# Olympus_v1.net
KiCad netlist of a schematic drawn in EAGLE
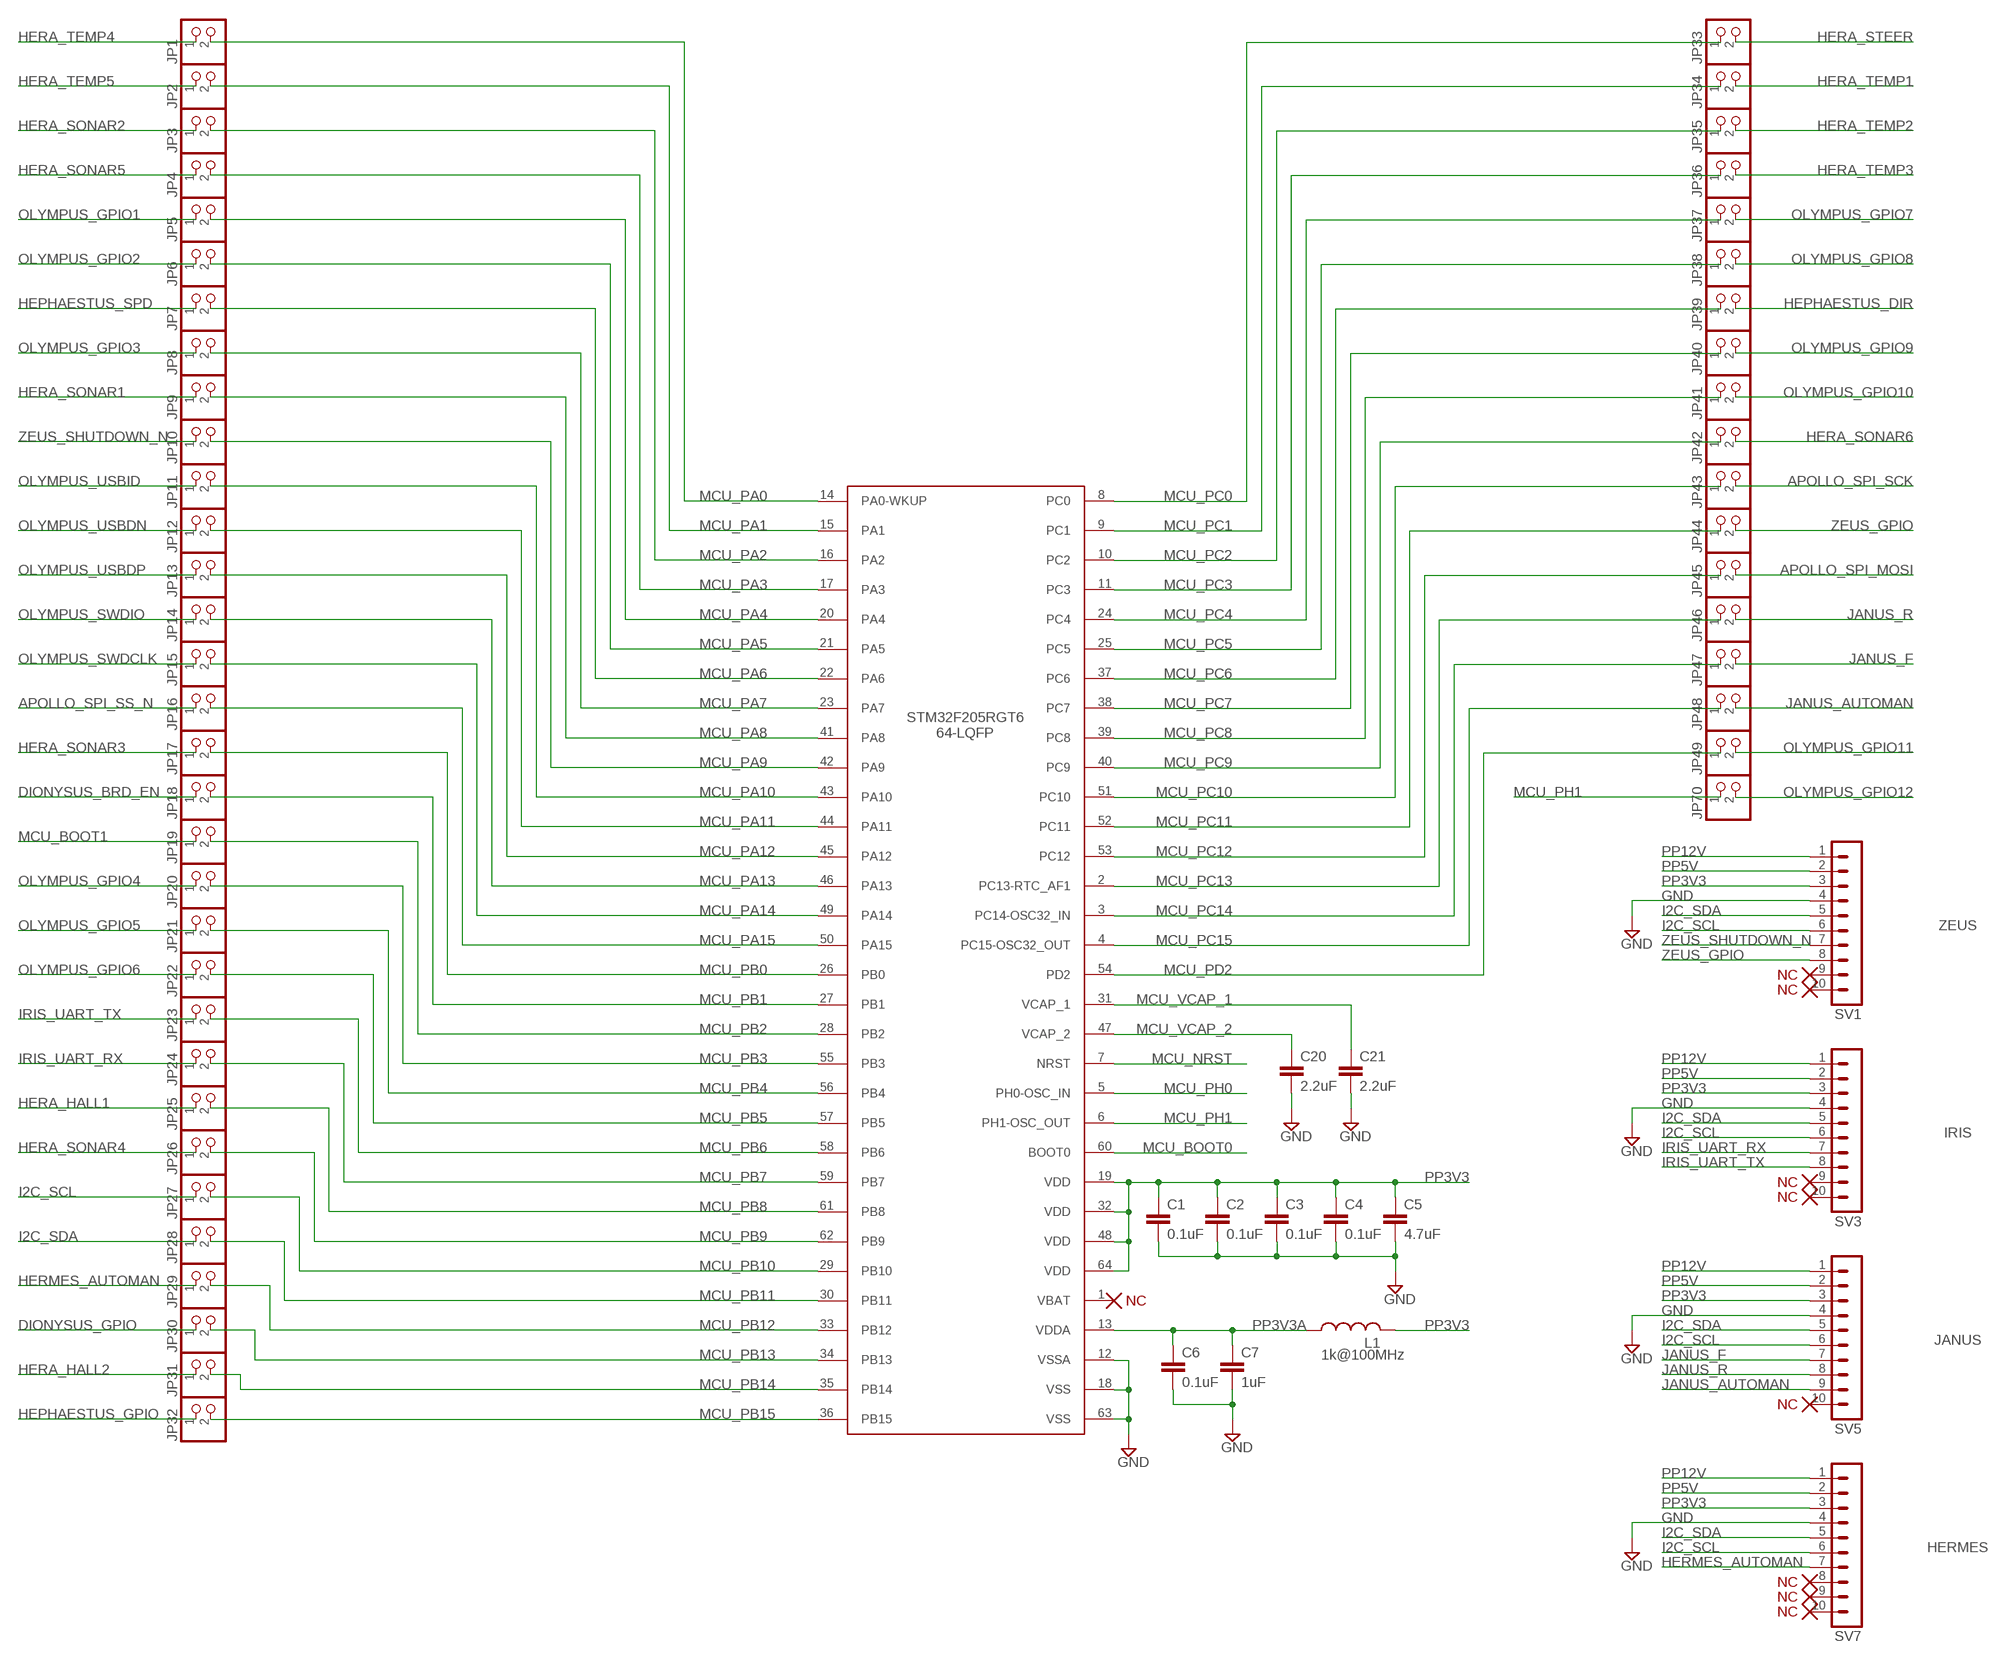
[diagram p0: schematic, sheet 1, part 1 of 2]
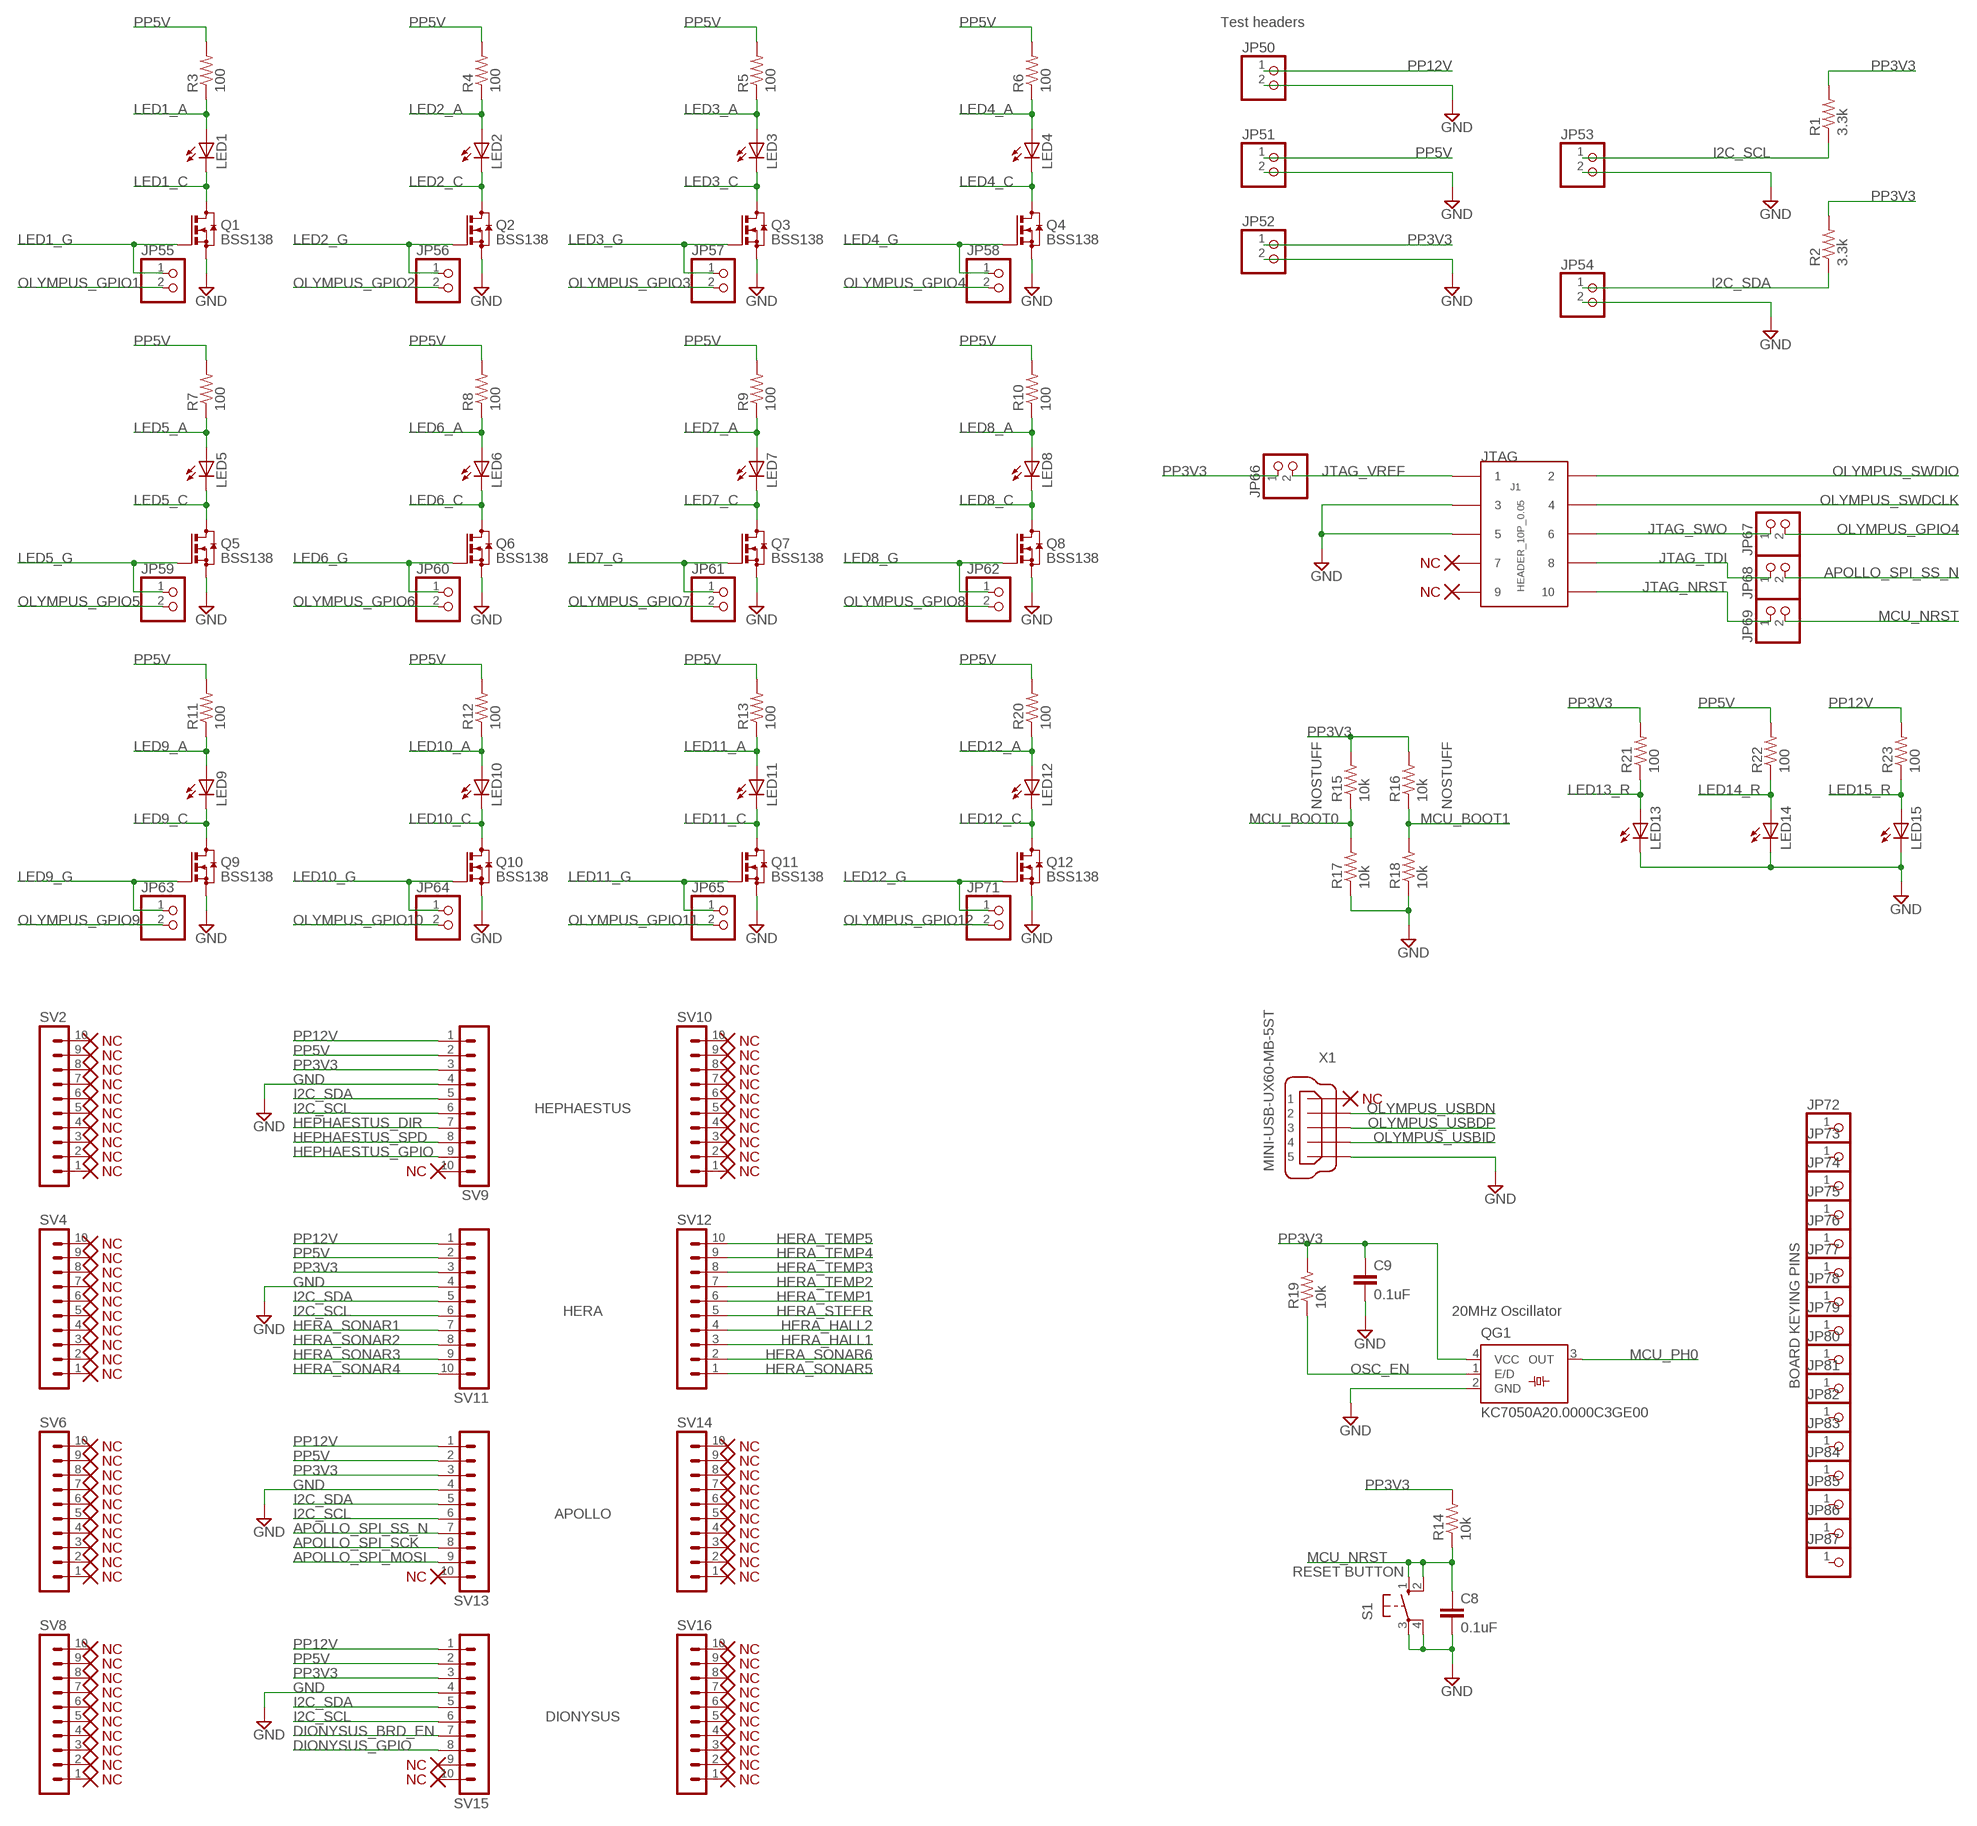
[diagram p1: schematic, sheet 1, part 2 of 2]

(export (version "E")
  (design (tool "Eeschema 10.0.6"))
  (components
    (comp (ref "C1")
      (value "0.1uF")
      (footprint "eagle-import:C0402")
      (libsource (lib "eagle-import") (part "C-EUC0402"))
    )
    (comp (ref "C2")
      (value "0.1uF")
      (footprint "eagle-import:C0402")
      (libsource (lib "eagle-import") (part "C-EUC0402"))
    )
    (comp (ref "C3")
      (value "0.1uF")
      (footprint "eagle-import:C0402")
      (libsource (lib "eagle-import") (part "C-EUC0402"))
    )
    (comp (ref "C4")
      (value "0.1uF")
      (footprint "eagle-import:C0402")
      (libsource (lib "eagle-import") (part "C-EUC0402"))
    )
    (comp (ref "C5")
      (value "4.7uF")
      (footprint "eagle-import:C0603")
      (libsource (lib "eagle-import") (part "C-EUC0603"))
    )
    (comp (ref "C6")
      (value "0.1uF")
      (footprint "eagle-import:C0402")
      (libsource (lib "eagle-import") (part "C-EUC0402"))
    )
    (comp (ref "C7")
      (value "1uF")
      (footprint "eagle-import:C0603")
      (libsource (lib "eagle-import") (part "C-EUC0603"))
    )
    (comp (ref "C8")
      (value "0.1uF")
      (footprint "eagle-import:C0402")
      (libsource (lib "eagle-import") (part "C-EUC0402"))
    )
    (comp (ref "C9")
      (value "0.1uF")
      (footprint "eagle-import:C0402")
      (libsource (lib "eagle-import") (part "C-EUC0402"))
    )
    (comp (ref "C20")
      (value "2.2uF")
      (footprint "eagle-import:C0402")
      (libsource (lib "eagle-import") (part "C-EUC0402"))
    )
    (comp (ref "C21")
      (value "2.2uF")
      (footprint "eagle-import:C0402")
      (libsource (lib "eagle-import") (part "C-EUC0402"))
    )
    (comp (ref "J1")
      (value "HEADER_10P_0.05")
      (footprint "eagle-import:HEADER_10P_0.05")
      (libsource (lib "eagle-import") (part "HEADER_10P_0.05"))
    )
    (comp (ref "JP1")
      (value "PINHD-1X2")
      (footprint "eagle-import:1X02")
      (libsource (lib "eagle-import") (part "PINHD-1X2"))
    )
    (comp (ref "JP2")
      (value "PINHD-1X2")
      (footprint "eagle-import:1X02")
      (libsource (lib "eagle-import") (part "PINHD-1X2"))
    )
    (comp (ref "JP3")
      (value "PINHD-1X2")
      (footprint "eagle-import:1X02")
      (libsource (lib "eagle-import") (part "PINHD-1X2"))
    )
    (comp (ref "JP4")
      (value "PINHD-1X2")
      (footprint "eagle-import:1X02")
      (libsource (lib "eagle-import") (part "PINHD-1X2"))
    )
    (comp (ref "JP5")
      (value "PINHD-1X2")
      (footprint "eagle-import:1X02")
      (libsource (lib "eagle-import") (part "PINHD-1X2"))
    )
    (comp (ref "JP6")
      (value "PINHD-1X2")
      (footprint "eagle-import:1X02")
      (libsource (lib "eagle-import") (part "PINHD-1X2"))
    )
    (comp (ref "JP7")
      (value "PINHD-1X2")
      (footprint "eagle-import:1X02")
      (libsource (lib "eagle-import") (part "PINHD-1X2"))
    )
    (comp (ref "JP8")
      (value "PINHD-1X2")
      (footprint "eagle-import:1X02")
      (libsource (lib "eagle-import") (part "PINHD-1X2"))
    )
    (comp (ref "JP9")
      (value "PINHD-1X2")
      (footprint "eagle-import:1X02")
      (libsource (lib "eagle-import") (part "PINHD-1X2"))
    )
    (comp (ref "JP10")
      (value "PINHD-1X2")
      (footprint "eagle-import:1X02")
      (libsource (lib "eagle-import") (part "PINHD-1X2"))
    )
    (comp (ref "JP11")
      (value "PINHD-1X2")
      (footprint "eagle-import:1X02")
      (libsource (lib "eagle-import") (part "PINHD-1X2"))
    )
    (comp (ref "JP12")
      (value "PINHD-1X2")
      (footprint "eagle-import:1X02")
      (libsource (lib "eagle-import") (part "PINHD-1X2"))
    )
    (comp (ref "JP13")
      (value "PINHD-1X2")
      (footprint "eagle-import:1X02")
      (libsource (lib "eagle-import") (part "PINHD-1X2"))
    )
    (comp (ref "JP14")
      (value "PINHD-1X2")
      (footprint "eagle-import:1X02")
      (libsource (lib "eagle-import") (part "PINHD-1X2"))
    )
    (comp (ref "JP15")
      (value "PINHD-1X2")
      (footprint "eagle-import:1X02")
      (libsource (lib "eagle-import") (part "PINHD-1X2"))
    )
    (comp (ref "JP16")
      (value "PINHD-1X2")
      (footprint "eagle-import:1X02")
      (libsource (lib "eagle-import") (part "PINHD-1X2"))
    )
    (comp (ref "JP17")
      (value "PINHD-1X2")
      (footprint "eagle-import:1X02")
      (libsource (lib "eagle-import") (part "PINHD-1X2"))
    )
    (comp (ref "JP18")
      (value "PINHD-1X2")
      (footprint "eagle-import:1X02")
      (libsource (lib "eagle-import") (part "PINHD-1X2"))
    )
    (comp (ref "JP19")
      (value "PINHD-1X2")
      (footprint "eagle-import:1X02")
      (libsource (lib "eagle-import") (part "PINHD-1X2"))
    )
    (comp (ref "JP20")
      (value "PINHD-1X2")
      (footprint "eagle-import:1X02")
      (libsource (lib "eagle-import") (part "PINHD-1X2"))
    )
    (comp (ref "JP21")
      (value "PINHD-1X2")
      (footprint "eagle-import:1X02")
      (libsource (lib "eagle-import") (part "PINHD-1X2"))
    )
    (comp (ref "JP22")
      (value "PINHD-1X2")
      (footprint "eagle-import:1X02")
      (libsource (lib "eagle-import") (part "PINHD-1X2"))
    )
    (comp (ref "JP23")
      (value "PINHD-1X2")
      (footprint "eagle-import:1X02")
      (libsource (lib "eagle-import") (part "PINHD-1X2"))
    )
    (comp (ref "JP24")
      (value "PINHD-1X2")
      (footprint "eagle-import:1X02")
      (libsource (lib "eagle-import") (part "PINHD-1X2"))
    )
    (comp (ref "JP25")
      (value "PINHD-1X2")
      (footprint "eagle-import:1X02")
      (libsource (lib "eagle-import") (part "PINHD-1X2"))
    )
    (comp (ref "JP26")
      (value "PINHD-1X2")
      (footprint "eagle-import:1X02")
      (libsource (lib "eagle-import") (part "PINHD-1X2"))
    )
    (comp (ref "JP27")
      (value "PINHD-1X2")
      (footprint "eagle-import:1X02")
      (libsource (lib "eagle-import") (part "PINHD-1X2"))
    )
    (comp (ref "JP28")
      (value "PINHD-1X2")
      (footprint "eagle-import:1X02")
      (libsource (lib "eagle-import") (part "PINHD-1X2"))
    )
    (comp (ref "JP29")
      (value "PINHD-1X2")
      (footprint "eagle-import:1X02")
      (libsource (lib "eagle-import") (part "PINHD-1X2"))
    )
    (comp (ref "JP30")
      (value "PINHD-1X2")
      (footprint "eagle-import:1X02")
      (libsource (lib "eagle-import") (part "PINHD-1X2"))
    )
    (comp (ref "JP31")
      (value "PINHD-1X2")
      (footprint "eagle-import:1X02")
      (libsource (lib "eagle-import") (part "PINHD-1X2"))
    )
    (comp (ref "JP32")
      (value "PINHD-1X2")
      (footprint "eagle-import:1X02")
      (libsource (lib "eagle-import") (part "PINHD-1X2"))
    )
    (comp (ref "JP33")
      (value "PINHD-1X2")
      (footprint "eagle-import:1X02")
      (libsource (lib "eagle-import") (part "PINHD-1X2"))
    )
    (comp (ref "JP34")
      (value "PINHD-1X2")
      (footprint "eagle-import:1X02")
      (libsource (lib "eagle-import") (part "PINHD-1X2"))
    )
    (comp (ref "JP35")
      (value "PINHD-1X2")
      (footprint "eagle-import:1X02")
      (libsource (lib "eagle-import") (part "PINHD-1X2"))
    )
    (comp (ref "JP36")
      (value "PINHD-1X2")
      (footprint "eagle-import:1X02")
      (libsource (lib "eagle-import") (part "PINHD-1X2"))
    )
    (comp (ref "JP37")
      (value "PINHD-1X2")
      (footprint "eagle-import:1X02")
      (libsource (lib "eagle-import") (part "PINHD-1X2"))
    )
    (comp (ref "JP38")
      (value "PINHD-1X2")
      (footprint "eagle-import:1X02")
      (libsource (lib "eagle-import") (part "PINHD-1X2"))
    )
    (comp (ref "JP39")
      (value "PINHD-1X2")
      (footprint "eagle-import:1X02")
      (libsource (lib "eagle-import") (part "PINHD-1X2"))
    )
    (comp (ref "JP40")
      (value "PINHD-1X2")
      (footprint "eagle-import:1X02")
      (libsource (lib "eagle-import") (part "PINHD-1X2"))
    )
    (comp (ref "JP41")
      (value "PINHD-1X2")
      (footprint "eagle-import:1X02")
      (libsource (lib "eagle-import") (part "PINHD-1X2"))
    )
    (comp (ref "JP42")
      (value "PINHD-1X2")
      (footprint "eagle-import:1X02")
      (libsource (lib "eagle-import") (part "PINHD-1X2"))
    )
    (comp (ref "JP43")
      (value "PINHD-1X2")
      (footprint "eagle-import:1X02")
      (libsource (lib "eagle-import") (part "PINHD-1X2"))
    )
    (comp (ref "JP44")
      (value "PINHD-1X2")
      (footprint "eagle-import:1X02")
      (libsource (lib "eagle-import") (part "PINHD-1X2"))
    )
    (comp (ref "JP45")
      (value "PINHD-1X2")
      (footprint "eagle-import:1X02")
      (libsource (lib "eagle-import") (part "PINHD-1X2"))
    )
    (comp (ref "JP46")
      (value "PINHD-1X2")
      (footprint "eagle-import:1X02")
      (libsource (lib "eagle-import") (part "PINHD-1X2"))
    )
    (comp (ref "JP47")
      (value "PINHD-1X2")
      (footprint "eagle-import:1X02")
      (libsource (lib "eagle-import") (part "PINHD-1X2"))
    )
    (comp (ref "JP48")
      (value "PINHD-1X2")
      (footprint "eagle-import:1X02")
      (libsource (lib "eagle-import") (part "PINHD-1X2"))
    )
    (comp (ref "JP49")
      (value "PINHD-1X2")
      (footprint "eagle-import:1X02")
      (libsource (lib "eagle-import") (part "PINHD-1X2"))
    )
    (comp (ref "JP50")
      (value "PINHD-1X2")
      (footprint "eagle-import:1X02")
      (libsource (lib "eagle-import") (part "PINHD-1X2"))
    )
    (comp (ref "JP51")
      (value "PINHD-1X2")
      (footprint "eagle-import:1X02")
      (libsource (lib "eagle-import") (part "PINHD-1X2"))
    )
    (comp (ref "JP52")
      (value "PINHD-1X2")
      (footprint "eagle-import:1X02")
      (libsource (lib "eagle-import") (part "PINHD-1X2"))
    )
    (comp (ref "JP53")
      (value "PINHD-1X2")
      (footprint "eagle-import:1X02")
      (libsource (lib "eagle-import") (part "PINHD-1X2"))
    )
    (comp (ref "JP54")
      (value "PINHD-1X2")
      (footprint "eagle-import:1X02")
      (libsource (lib "eagle-import") (part "PINHD-1X2"))
    )
    (comp (ref "JP55")
      (value "PINHD-1X2")
      (footprint "eagle-import:1X02")
      (libsource (lib "eagle-import") (part "PINHD-1X2"))
    )
    (comp (ref "JP56")
      (value "PINHD-1X2")
      (footprint "eagle-import:1X02")
      (libsource (lib "eagle-import") (part "PINHD-1X2"))
    )
    (comp (ref "JP57")
      (value "PINHD-1X2")
      (footprint "eagle-import:1X02")
      (libsource (lib "eagle-import") (part "PINHD-1X2"))
    )
    (comp (ref "JP58")
      (value "PINHD-1X2")
      (footprint "eagle-import:1X02")
      (libsource (lib "eagle-import") (part "PINHD-1X2"))
    )
    (comp (ref "JP59")
      (value "PINHD-1X2")
      (footprint "eagle-import:1X02")
      (libsource (lib "eagle-import") (part "PINHD-1X2"))
    )
    (comp (ref "JP60")
      (value "PINHD-1X2")
      (footprint "eagle-import:1X02")
      (libsource (lib "eagle-import") (part "PINHD-1X2"))
    )
    (comp (ref "JP61")
      (value "PINHD-1X2")
      (footprint "eagle-import:1X02")
      (libsource (lib "eagle-import") (part "PINHD-1X2"))
    )
    (comp (ref "JP62")
      (value "PINHD-1X2")
      (footprint "eagle-import:1X02")
      (libsource (lib "eagle-import") (part "PINHD-1X2"))
    )
    (comp (ref "JP63")
      (value "PINHD-1X2")
      (footprint "eagle-import:1X02")
      (libsource (lib "eagle-import") (part "PINHD-1X2"))
    )
    (comp (ref "JP64")
      (value "PINHD-1X2")
      (footprint "eagle-import:1X02")
      (libsource (lib "eagle-import") (part "PINHD-1X2"))
    )
    (comp (ref "JP65")
      (value "PINHD-1X2")
      (footprint "eagle-import:1X02")
      (libsource (lib "eagle-import") (part "PINHD-1X2"))
    )
    (comp (ref "JP66")
      (value "PINHD-1X2")
      (footprint "eagle-import:1X02")
      (libsource (lib "eagle-import") (part "PINHD-1X2"))
    )
    (comp (ref "JP67")
      (value "PINHD-1X2")
      (footprint "eagle-import:1X02")
      (libsource (lib "eagle-import") (part "PINHD-1X2"))
    )
    (comp (ref "JP68")
      (value "PINHD-1X2")
      (footprint "eagle-import:1X02")
      (libsource (lib "eagle-import") (part "PINHD-1X2"))
    )
    (comp (ref "JP69")
      (value "PINHD-1X2")
      (footprint "eagle-import:1X02")
      (libsource (lib "eagle-import") (part "PINHD-1X2"))
    )
    (comp (ref "JP70")
      (value "PINHD-1X2")
      (footprint "eagle-import:1X02")
      (libsource (lib "eagle-import") (part "PINHD-1X2"))
    )
    (comp (ref "JP71")
      (value "PINHD-1X2")
      (footprint "eagle-import:1X02")
      (libsource (lib "eagle-import") (part "PINHD-1X2"))
    )
    (comp (ref "JP72")
      (value "PINHD-1X1")
      (footprint "eagle-import:1X01")
      (libsource (lib "eagle-import") (part "PINHD-1X1"))
    )
    (comp (ref "JP73")
      (value "PINHD-1X1")
      (footprint "eagle-import:1X01")
      (libsource (lib "eagle-import") (part "PINHD-1X1"))
    )
    (comp (ref "JP74")
      (value "PINHD-1X1")
      (footprint "eagle-import:1X01")
      (libsource (lib "eagle-import") (part "PINHD-1X1"))
    )
    (comp (ref "JP75")
      (value "PINHD-1X1")
      (footprint "eagle-import:1X01")
      (libsource (lib "eagle-import") (part "PINHD-1X1"))
    )
    (comp (ref "JP76")
      (value "PINHD-1X1")
      (footprint "eagle-import:1X01")
      (libsource (lib "eagle-import") (part "PINHD-1X1"))
    )
    (comp (ref "JP77")
      (value "PINHD-1X1")
      (footprint "eagle-import:1X01")
      (libsource (lib "eagle-import") (part "PINHD-1X1"))
    )
    (comp (ref "JP78")
      (value "PINHD-1X1")
      (footprint "eagle-import:1X01")
      (libsource (lib "eagle-import") (part "PINHD-1X1"))
    )
    (comp (ref "JP79")
      (value "PINHD-1X1")
      (footprint "eagle-import:1X01")
      (libsource (lib "eagle-import") (part "PINHD-1X1"))
    )
    (comp (ref "JP80")
      (value "PINHD-1X1")
      (footprint "eagle-import:1X01")
      (libsource (lib "eagle-import") (part "PINHD-1X1"))
    )
    (comp (ref "JP81")
      (value "PINHD-1X1")
      (footprint "eagle-import:1X01")
      (libsource (lib "eagle-import") (part "PINHD-1X1"))
    )
    (comp (ref "JP82")
      (value "PINHD-1X1")
      (footprint "eagle-import:1X01")
      (libsource (lib "eagle-import") (part "PINHD-1X1"))
    )
    (comp (ref "JP83")
      (value "PINHD-1X1")
      (footprint "eagle-import:1X01")
      (libsource (lib "eagle-import") (part "PINHD-1X1"))
    )
    (comp (ref "JP84")
      (value "PINHD-1X1")
      (footprint "eagle-import:1X01")
      (libsource (lib "eagle-import") (part "PINHD-1X1"))
    )
    (comp (ref "JP85")
      (value "PINHD-1X1")
      (footprint "eagle-import:1X01")
      (libsource (lib "eagle-import") (part "PINHD-1X1"))
    )
    (comp (ref "JP86")
      (value "PINHD-1X1")
      (footprint "eagle-import:1X01")
      (libsource (lib "eagle-import") (part "PINHD-1X1"))
    )
    (comp (ref "JP87")
      (value "PINHD-1X1")
      (footprint "eagle-import:1X01")
      (libsource (lib "eagle-import") (part "PINHD-1X1"))
    )
    (comp (ref "L1")
      (value "L-USL0201")
      (footprint "eagle-import:L0201")
      (libsource (lib "eagle-import") (part "L-USL0201"))
    )
    (comp (ref "LED1")
      (value "LEDCHIP-LED0603")
      (footprint "eagle-import:CHIP-LED0603")
      (libsource (lib "eagle-import") (part "LEDCHIP-LED0603"))
    )
    (comp (ref "LED2")
      (value "LEDCHIP-LED0603")
      (footprint "eagle-import:CHIP-LED0603")
      (libsource (lib "eagle-import") (part "LEDCHIP-LED0603"))
    )
    (comp (ref "LED3")
      (value "LEDCHIP-LED0603")
      (footprint "eagle-import:CHIP-LED0603")
      (libsource (lib "eagle-import") (part "LEDCHIP-LED0603"))
    )
    (comp (ref "LED4")
      (value "LEDCHIP-LED0603")
      (footprint "eagle-import:CHIP-LED0603")
      (libsource (lib "eagle-import") (part "LEDCHIP-LED0603"))
    )
    (comp (ref "LED5")
      (value "LEDCHIP-LED0603")
      (footprint "eagle-import:CHIP-LED0603")
      (libsource (lib "eagle-import") (part "LEDCHIP-LED0603"))
    )
    (comp (ref "LED6")
      (value "LEDCHIP-LED0603")
      (footprint "eagle-import:CHIP-LED0603")
      (libsource (lib "eagle-import") (part "LEDCHIP-LED0603"))
    )
    (comp (ref "LED7")
      (value "LEDCHIP-LED0603")
      (footprint "eagle-import:CHIP-LED0603")
      (libsource (lib "eagle-import") (part "LEDCHIP-LED0603"))
    )
    (comp (ref "LED8")
      (value "LEDCHIP-LED0603")
      (footprint "eagle-import:CHIP-LED0603")
      (libsource (lib "eagle-import") (part "LEDCHIP-LED0603"))
    )
    (comp (ref "LED9")
      (value "LEDCHIP-LED0603")
      (footprint "eagle-import:CHIP-LED0603")
      (libsource (lib "eagle-import") (part "LEDCHIP-LED0603"))
    )
    (comp (ref "LED10")
      (value "LEDCHIP-LED0603")
      (footprint "eagle-import:CHIP-LED0603")
      (libsource (lib "eagle-import") (part "LEDCHIP-LED0603"))
    )
    (comp (ref "LED11")
      (value "LEDCHIP-LED0603")
      (footprint "eagle-import:CHIP-LED0603")
      (libsource (lib "eagle-import") (part "LEDCHIP-LED0603"))
    )
    (comp (ref "LED12")
      (value "LEDCHIP-LED0603")
      (footprint "eagle-import:CHIP-LED0603")
      (libsource (lib "eagle-import") (part "LEDCHIP-LED0603"))
    )
    (comp (ref "LED13")
      (value "LEDCHIP-LED0603")
      (footprint "eagle-import:CHIP-LED0603")
      (libsource (lib "eagle-import") (part "LEDCHIP-LED0603"))
    )
    (comp (ref "LED14")
      (value "LEDCHIP-LED0603")
      (footprint "eagle-import:CHIP-LED0603")
      (libsource (lib "eagle-import") (part "LEDCHIP-LED0603"))
    )
    (comp (ref "LED15")
      (value "LEDCHIP-LED0603")
      (footprint "eagle-import:CHIP-LED0603")
      (libsource (lib "eagle-import") (part "LEDCHIP-LED0603"))
    )
    (comp (ref "Q1")
      (value "BSS138")
      (footprint "eagle-import:SOT23")
      (libsource (lib "eagle-import") (part "BSS123"))
    )
    (comp (ref "Q2")
      (value "BSS138")
      (footprint "eagle-import:SOT23")
      (libsource (lib "eagle-import") (part "BSS123"))
    )
    (comp (ref "Q3")
      (value "BSS138")
      (footprint "eagle-import:SOT23")
      (libsource (lib "eagle-import") (part "BSS123"))
    )
    (comp (ref "Q4")
      (value "BSS138")
      (footprint "eagle-import:SOT23")
      (libsource (lib "eagle-import") (part "BSS123"))
    )
    (comp (ref "Q5")
      (value "BSS138")
      (footprint "eagle-import:SOT23")
      (libsource (lib "eagle-import") (part "BSS123"))
    )
    (comp (ref "Q6")
      (value "BSS138")
      (footprint "eagle-import:SOT23")
      (libsource (lib "eagle-import") (part "BSS123"))
    )
    (comp (ref "Q7")
      (value "BSS138")
      (footprint "eagle-import:SOT23")
      (libsource (lib "eagle-import") (part "BSS123"))
    )
    (comp (ref "Q8")
      (value "BSS138")
      (footprint "eagle-import:SOT23")
      (libsource (lib "eagle-import") (part "BSS123"))
    )
    (comp (ref "Q9")
      (value "BSS138")
      (footprint "eagle-import:SOT23")
      (libsource (lib "eagle-import") (part "BSS123"))
    )
    (comp (ref "Q10")
      (value "BSS138")
      (footprint "eagle-import:SOT23")
      (libsource (lib "eagle-import") (part "BSS123"))
    )
    (comp (ref "Q11")
      (value "BSS138")
      (footprint "eagle-import:SOT23")
      (libsource (lib "eagle-import") (part "BSS123"))
    )
    (comp (ref "Q12")
      (value "BSS138")
      (footprint "eagle-import:SOT23")
      (libsource (lib "eagle-import") (part "BSS123"))
    )
    (comp (ref "QG1")
      (value "KC7050A20.0000C3GE00")
      (footprint "eagle-import:SM77H")
      (libsource (lib "eagle-import") (part "SM77H"))
    )
    (comp (ref "R1")
      (value "3.3k")
      (footprint "eagle-import:R0603")
      (libsource (lib "eagle-import") (part "R-US_R0603"))
    )
    (comp (ref "R2")
      (value "3.3k")
      (footprint "eagle-import:R0603")
      (libsource (lib "eagle-import") (part "R-US_R0603"))
    )
    (comp (ref "R3")
      (value "100")
      (footprint "eagle-import:R0603")
      (libsource (lib "eagle-import") (part "resistor_R-US_R0603"))
    )
    (comp (ref "R4")
      (value "100")
      (footprint "eagle-import:R0603")
      (libsource (lib "eagle-import") (part "resistor_R-US_R0603"))
    )
    (comp (ref "R5")
      (value "100")
      (footprint "eagle-import:R0603")
      (libsource (lib "eagle-import") (part "resistor_R-US_R0603"))
    )
    (comp (ref "R6")
      (value "100")
      (footprint "eagle-import:R0603")
      (libsource (lib "eagle-import") (part "resistor_R-US_R0603"))
    )
    (comp (ref "R7")
      (value "100")
      (footprint "eagle-import:R0603")
      (libsource (lib "eagle-import") (part "resistor_R-US_R0603"))
    )
    (comp (ref "R8")
      (value "100")
      (footprint "eagle-import:R0603")
      (libsource (lib "eagle-import") (part "resistor_R-US_R0603"))
    )
    (comp (ref "R9")
      (value "100")
      (footprint "eagle-import:R0603")
      (libsource (lib "eagle-import") (part "resistor_R-US_R0603"))
    )
    (comp (ref "R10")
      (value "100")
      (footprint "eagle-import:R0603")
      (libsource (lib "eagle-import") (part "resistor_R-US_R0603"))
    )
    (comp (ref "R11")
      (value "100")
      (footprint "eagle-import:R0603")
      (libsource (lib "eagle-import") (part "resistor_R-US_R0603"))
    )
    (comp (ref "R12")
      (value "100")
      (footprint "eagle-import:R0603")
      (libsource (lib "eagle-import") (part "resistor_R-US_R0603"))
    )
    (comp (ref "R13")
      (value "100")
      (footprint "eagle-import:R0603")
      (libsource (lib "eagle-import") (part "resistor_R-US_R0603"))
    )
    (comp (ref "R14")
      (value "10k")
      (footprint "eagle-import:R0603")
      (libsource (lib "eagle-import") (part "R-US_R0603"))
    )
    (comp (ref "R15")
      (value "10k")
      (footprint "eagle-import:R0603")
      (fields (field (name "BOMOPTION") "NOSTUFF"))
      (libsource (lib "eagle-import") (part "R-US_R0603"))
    )
    (comp (ref "R16")
      (value "10k")
      (footprint "eagle-import:R0603")
      (fields (field (name "BOMOPTION") "NOSTUFF"))
      (libsource (lib "eagle-import") (part "R-US_R0603"))
    )
    (comp (ref "R17")
      (value "10k")
      (footprint "eagle-import:R0603")
      (libsource (lib "eagle-import") (part "R-US_R0603"))
    )
    (comp (ref "R18")
      (value "10k")
      (footprint "eagle-import:R0603")
      (libsource (lib "eagle-import") (part "R-US_R0603"))
    )
    (comp (ref "R19")
      (value "10k")
      (footprint "eagle-import:R0603")
      (libsource (lib "eagle-import") (part "R-US_R0603"))
    )
    (comp (ref "R20")
      (value "100")
      (footprint "eagle-import:R0603")
      (libsource (lib "eagle-import") (part "resistor_R-US_R0603"))
    )
    (comp (ref "R21")
      (value "100")
      (footprint "eagle-import:R0603")
      (libsource (lib "eagle-import") (part "resistor_R-US_R0603"))
    )
    (comp (ref "R22")
      (value "100")
      (footprint "eagle-import:R0603")
      (libsource (lib "eagle-import") (part "resistor_R-US_R0603"))
    )
    (comp (ref "R23")
      (value "100")
      (footprint "eagle-import:R0603")
      (libsource (lib "eagle-import") (part "resistor_R-US_R0603"))
    )
    (comp (ref "S1")
      (value "10-XX")
      (footprint "eagle-import:B3F-10XX")
      (fields (field (name "MPN") "B3F-1000"))
      (libsource (lib "eagle-import") (part "10-XX"))
    )
    (comp (ref "SV1")
      (value "MA10-1")
      (footprint "eagle-import:MA10-1")
      (libsource (lib "eagle-import") (part "MA10-1"))
    )
    (comp (ref "SV2")
      (value "MA10-1")
      (footprint "eagle-import:MA10-1")
      (libsource (lib "eagle-import") (part "MA10-1"))
    )
    (comp (ref "SV3")
      (value "MA10-1")
      (footprint "eagle-import:MA10-1")
      (libsource (lib "eagle-import") (part "MA10-1"))
    )
    (comp (ref "SV4")
      (value "MA10-1")
      (footprint "eagle-import:MA10-1")
      (libsource (lib "eagle-import") (part "MA10-1"))
    )
    (comp (ref "SV5")
      (value "MA10-1")
      (footprint "eagle-import:MA10-1")
      (libsource (lib "eagle-import") (part "MA10-1"))
    )
    (comp (ref "SV6")
      (value "MA10-1")
      (footprint "eagle-import:MA10-1")
      (libsource (lib "eagle-import") (part "MA10-1"))
    )
    (comp (ref "SV7")
      (value "MA10-1")
      (footprint "eagle-import:MA10-1")
      (libsource (lib "eagle-import") (part "MA10-1"))
    )
    (comp (ref "SV8")
      (value "MA10-1")
      (footprint "eagle-import:MA10-1")
      (libsource (lib "eagle-import") (part "MA10-1"))
    )
    (comp (ref "SV9")
      (value "MA10-1")
      (footprint "eagle-import:MA10-1")
      (libsource (lib "eagle-import") (part "MA10-1"))
    )
    (comp (ref "SV10")
      (value "MA10-1")
      (footprint "eagle-import:MA10-1")
      (libsource (lib "eagle-import") (part "MA10-1"))
    )
    (comp (ref "SV11")
      (value "MA10-1")
      (footprint "eagle-import:MA10-1")
      (libsource (lib "eagle-import") (part "MA10-1"))
    )
    (comp (ref "SV12")
      (value "MA10-1")
      (footprint "eagle-import:MA10-1")
      (libsource (lib "eagle-import") (part "MA10-1"))
    )
    (comp (ref "SV13")
      (value "MA10-1")
      (footprint "eagle-import:MA10-1")
      (libsource (lib "eagle-import") (part "MA10-1"))
    )
    (comp (ref "SV14")
      (value "MA10-1")
      (footprint "eagle-import:MA10-1")
      (libsource (lib "eagle-import") (part "MA10-1"))
    )
    (comp (ref "SV15")
      (value "MA10-1")
      (footprint "eagle-import:MA10-1")
      (libsource (lib "eagle-import") (part "MA10-1"))
    )
    (comp (ref "SV16")
      (value "MA10-1")
      (footprint "eagle-import:MA10-1")
      (libsource (lib "eagle-import") (part "MA10-1"))
    )
    (comp (ref "U1")
      (value "STM32F205RGT6")
      (footprint "eagle-import:LQFP-ST-64-2")
      (libsource (lib "eagle-import") (part "STM32F205RGT6"))
    )
    (comp (ref "X1")
      (value "MINI-USB-UX60-MB-5ST")
      (footprint "eagle-import:UX60-MB-5ST")
      (libsource (lib "eagle-import") (part "MINI-USB-UX60-MB-5ST"))
    )
  )
  (nets
    (net (code "1") (name "/APOLLO_SPI_MOSI") (class "Default")
      (node (ref "JP45") (pin "2") (pinfunction "2_2") (pintype "passive"))
      (node (ref "SV13") (pin "9") (pinfunction "9_9") (pintype "passive"))
    )
    (net (code "2") (name "/APOLLO_SPI_SCK") (class "Default")
      (node (ref "JP43") (pin "2") (pinfunction "2_2") (pintype "passive"))
      (node (ref "SV13") (pin "8") (pinfunction "8_8") (pintype "passive"))
    )
    (net (code "3") (name "/APOLLO_SPI_SS_N") (class "Default")
      (node (ref "JP16") (pin "1") (pinfunction "1_1") (pintype "passive"))
      (node (ref "JP68") (pin "2") (pinfunction "2_2") (pintype "passive"))
      (node (ref "SV13") (pin "7") (pinfunction "7_7") (pintype "passive"))
    )
    (net (code "4") (name "/DIONYSUS_BRD_EN") (class "Default")
      (node (ref "JP18") (pin "1") (pinfunction "1_1") (pintype "passive"))
      (node (ref "SV15") (pin "7") (pinfunction "7_7") (pintype "passive"))
    )
    (net (code "5") (name "/DIONYSUS_GPIO") (class "Default")
      (node (ref "JP30") (pin "1") (pinfunction "1_1") (pintype "passive"))
      (node (ref "SV15") (pin "8") (pinfunction "8_8") (pintype "passive"))
    )
    (net (code "6") (name "/HEPHAESTUS_DIR") (class "Default")
      (node (ref "JP39") (pin "2") (pinfunction "2_2") (pintype "passive"))
      (node (ref "SV9") (pin "7") (pinfunction "7_7") (pintype "passive"))
    )
    (net (code "7") (name "/HEPHAESTUS_GPIO") (class "Default")
      (node (ref "JP32") (pin "1") (pinfunction "1_1") (pintype "passive"))
      (node (ref "SV9") (pin "9") (pinfunction "9_9") (pintype "passive"))
    )
    (net (code "8") (name "/HEPHAESTUS_SPD") (class "Default")
      (node (ref "JP7") (pin "1") (pinfunction "1_1") (pintype "passive"))
      (node (ref "SV9") (pin "8") (pinfunction "8_8") (pintype "passive"))
    )
    (net (code "9") (name "/HERA_HALL1") (class "Default")
      (node (ref "JP25") (pin "1") (pinfunction "1_1") (pintype "passive"))
      (node (ref "SV12") (pin "3") (pinfunction "3_3") (pintype "passive"))
    )
    (net (code "10") (name "/HERA_HALL2") (class "Default")
      (node (ref "JP31") (pin "1") (pinfunction "1_1") (pintype "passive"))
      (node (ref "SV12") (pin "4") (pinfunction "4_4") (pintype "passive"))
    )
    (net (code "11") (name "/HERA_SONAR1") (class "Default")
      (node (ref "JP9") (pin "1") (pinfunction "1_1") (pintype "passive"))
      (node (ref "SV11") (pin "7") (pinfunction "7_7") (pintype "passive"))
    )
    (net (code "12") (name "/HERA_SONAR2") (class "Default")
      (node (ref "JP3") (pin "1") (pinfunction "1_1") (pintype "passive"))
      (node (ref "SV11") (pin "8") (pinfunction "8_8") (pintype "passive"))
    )
    (net (code "13") (name "/HERA_SONAR3") (class "Default")
      (node (ref "JP17") (pin "1") (pinfunction "1_1") (pintype "passive"))
      (node (ref "SV11") (pin "9") (pinfunction "9_9") (pintype "passive"))
    )
    (net (code "14") (name "/HERA_SONAR4") (class "Default")
      (node (ref "JP26") (pin "1") (pinfunction "1_1") (pintype "passive"))
      (node (ref "SV11") (pin "10") (pinfunction "10_10") (pintype "passive"))
    )
    (net (code "15") (name "/HERA_SONAR5") (class "Default")
      (node (ref "JP4") (pin "1") (pinfunction "1_1") (pintype "passive"))
      (node (ref "SV12") (pin "1") (pinfunction "1_1") (pintype "passive"))
    )
    (net (code "16") (name "/HERA_SONAR6") (class "Default")
      (node (ref "JP42") (pin "2") (pinfunction "2_2") (pintype "passive"))
      (node (ref "SV12") (pin "2") (pinfunction "2_2") (pintype "passive"))
    )
    (net (code "17") (name "/HERA_STEER") (class "Default")
      (node (ref "JP33") (pin "2") (pinfunction "2_2") (pintype "passive"))
      (node (ref "SV12") (pin "5") (pinfunction "5_5") (pintype "passive"))
    )
    (net (code "18") (name "/HERA_TEMP1") (class "Default")
      (node (ref "JP34") (pin "2") (pinfunction "2_2") (pintype "passive"))
      (node (ref "SV12") (pin "6") (pinfunction "6_6") (pintype "passive"))
    )
    (net (code "19") (name "/HERA_TEMP2") (class "Default")
      (node (ref "JP35") (pin "2") (pinfunction "2_2") (pintype "passive"))
      (node (ref "SV12") (pin "7") (pinfunction "7_7") (pintype "passive"))
    )
    (net (code "20") (name "/HERA_TEMP3") (class "Default")
      (node (ref "JP36") (pin "2") (pinfunction "2_2") (pintype "passive"))
      (node (ref "SV12") (pin "8") (pinfunction "8_8") (pintype "passive"))
    )
    (net (code "21") (name "/HERA_TEMP4") (class "Default")
      (node (ref "JP1") (pin "1") (pinfunction "1_1") (pintype "passive"))
      (node (ref "SV12") (pin "9") (pinfunction "9_9") (pintype "passive"))
    )
    (net (code "22") (name "/HERA_TEMP5") (class "Default")
      (node (ref "JP2") (pin "1") (pinfunction "1_1") (pintype "passive"))
      (node (ref "SV12") (pin "10") (pinfunction "10_10") (pintype "passive"))
    )
    (net (code "23") (name "/HERMES_AUTOMAN") (class "Default")
      (node (ref "JP29") (pin "1") (pinfunction "1_1") (pintype "passive"))
      (node (ref "SV7") (pin "7") (pinfunction "7_7") (pintype "passive"))
    )
    (net (code "24") (name "/I2C_SCL") (class "Default")
      (node (ref "JP27") (pin "1") (pinfunction "1_1") (pintype "passive"))
      (node (ref "JP53") (pin "1") (pinfunction "1_1") (pintype "passive"))
      (node (ref "R1") (pin "1") (pinfunction "1_1") (pintype "passive"))
      (node (ref "SV1") (pin "6") (pinfunction "6_6") (pintype "passive"))
      (node (ref "SV11") (pin "6") (pinfunction "6_6") (pintype "passive"))
      (node (ref "SV13") (pin "6") (pinfunction "6_6") (pintype "passive"))
      (node (ref "SV15") (pin "6") (pinfunction "6_6") (pintype "passive"))
      (node (ref "SV3") (pin "6") (pinfunction "6_6") (pintype "passive"))
      (node (ref "SV5") (pin "6") (pinfunction "6_6") (pintype "passive"))
      (node (ref "SV7") (pin "6") (pinfunction "6_6") (pintype "passive"))
      (node (ref "SV9") (pin "6") (pinfunction "6_6") (pintype "passive"))
    )
    (net (code "25") (name "/I2C_SDA") (class "Default")
      (node (ref "JP28") (pin "1") (pinfunction "1_1") (pintype "passive"))
      (node (ref "JP54") (pin "1") (pinfunction "1_1") (pintype "passive"))
      (node (ref "R2") (pin "1") (pinfunction "1_1") (pintype "passive"))
      (node (ref "SV1") (pin "5") (pinfunction "5_5") (pintype "passive"))
      (node (ref "SV11") (pin "5") (pinfunction "5_5") (pintype "passive"))
      (node (ref "SV13") (pin "5") (pinfunction "5_5") (pintype "passive"))
      (node (ref "SV15") (pin "5") (pinfunction "5_5") (pintype "passive"))
      (node (ref "SV3") (pin "5") (pinfunction "5_5") (pintype "passive"))
      (node (ref "SV5") (pin "5") (pinfunction "5_5") (pintype "passive"))
      (node (ref "SV7") (pin "5") (pinfunction "5_5") (pintype "passive"))
      (node (ref "SV9") (pin "5") (pinfunction "5_5") (pintype "passive"))
    )
    (net (code "26") (name "/IRIS_UART_RX") (class "Default")
      (node (ref "JP24") (pin "1") (pinfunction "1_1") (pintype "passive"))
      (node (ref "SV3") (pin "7") (pinfunction "7_7") (pintype "passive"))
    )
    (net (code "27") (name "/IRIS_UART_TX") (class "Default")
      (node (ref "JP23") (pin "1") (pinfunction "1_1") (pintype "passive"))
      (node (ref "SV3") (pin "8") (pinfunction "8_8") (pintype "passive"))
    )
    (net (code "28") (name "/JANUS_AUTOMAN") (class "Default")
      (node (ref "JP48") (pin "2") (pinfunction "2_2") (pintype "passive"))
      (node (ref "SV5") (pin "9") (pinfunction "9_9") (pintype "passive"))
    )
    (net (code "29") (name "/JANUS_F") (class "Default")
      (node (ref "JP47") (pin "2") (pinfunction "2_2") (pintype "passive"))
      (node (ref "SV5") (pin "7") (pinfunction "7_7") (pintype "passive"))
    )
    (net (code "30") (name "/JANUS_R") (class "Default")
      (node (ref "JP46") (pin "2") (pinfunction "2_2") (pintype "passive"))
      (node (ref "SV5") (pin "8") (pinfunction "8_8") (pintype "passive"))
    )
    (net (code "31") (name "/JTAG_NRST") (class "Default")
      (node (ref "J1") (pin "10") (pinfunction "10_10") (pintype "bidirectional"))
      (node (ref "JP69") (pin "1") (pinfunction "1_1") (pintype "passive"))
    )
    (net (code "32") (name "/JTAG_SWO") (class "Default")
      (node (ref "J1") (pin "6") (pinfunction "6_6") (pintype "bidirectional"))
      (node (ref "JP67") (pin "1") (pinfunction "1_1") (pintype "passive"))
    )
    (net (code "33") (name "/JTAG_TDI") (class "Default")
      (node (ref "J1") (pin "8") (pinfunction "8_8") (pintype "bidirectional"))
      (node (ref "JP68") (pin "1") (pinfunction "1_1") (pintype "passive"))
    )
    (net (code "34") (name "/JTAG_VREF") (class "Default")
      (node (ref "J1") (pin "1") (pinfunction "1_1") (pintype "bidirectional"))
      (node (ref "JP66") (pin "2") (pinfunction "2_2") (pintype "passive"))
    )
    (net (code "35") (name "/LED1_A") (class "Default")
      (node (ref "LED1") (pin "A") (pinfunction "A_A") (pintype "passive"))
      (node (ref "R3") (pin "1") (pinfunction "1_1") (pintype "passive"))
    )
    (net (code "36") (name "/LED1_C") (class "Default")
      (node (ref "LED1") (pin "C") (pinfunction "C_C") (pintype "passive"))
      (node (ref "Q1") (pin "3") (pinfunction "D_3") (pintype "passive"))
    )
    (net (code "37") (name "/LED1_G") (class "Default")
      (node (ref "JP55") (pin "1") (pinfunction "1_1") (pintype "passive"))
      (node (ref "Q1") (pin "1") (pinfunction "G_1") (pintype "passive"))
    )
    (net (code "38") (name "/LED2_A") (class "Default")
      (node (ref "LED2") (pin "A") (pinfunction "A_A") (pintype "passive"))
      (node (ref "R4") (pin "1") (pinfunction "1_1") (pintype "passive"))
    )
    (net (code "39") (name "/LED2_C") (class "Default")
      (node (ref "LED2") (pin "C") (pinfunction "C_C") (pintype "passive"))
      (node (ref "Q2") (pin "3") (pinfunction "D_3") (pintype "passive"))
    )
    (net (code "40") (name "/LED2_G") (class "Default")
      (node (ref "JP56") (pin "1") (pinfunction "1_1") (pintype "passive"))
      (node (ref "Q2") (pin "1") (pinfunction "G_1") (pintype "passive"))
    )
    (net (code "41") (name "/LED3_A") (class "Default")
      (node (ref "LED3") (pin "A") (pinfunction "A_A") (pintype "passive"))
      (node (ref "R5") (pin "1") (pinfunction "1_1") (pintype "passive"))
    )
    (net (code "42") (name "/LED3_C") (class "Default")
      (node (ref "LED3") (pin "C") (pinfunction "C_C") (pintype "passive"))
      (node (ref "Q3") (pin "3") (pinfunction "D_3") (pintype "passive"))
    )
    (net (code "43") (name "/LED3_G") (class "Default")
      (node (ref "JP57") (pin "1") (pinfunction "1_1") (pintype "passive"))
      (node (ref "Q3") (pin "1") (pinfunction "G_1") (pintype "passive"))
    )
    (net (code "44") (name "/LED4_A") (class "Default")
      (node (ref "LED4") (pin "A") (pinfunction "A_A") (pintype "passive"))
      (node (ref "R6") (pin "1") (pinfunction "1_1") (pintype "passive"))
    )
    (net (code "45") (name "/LED4_C") (class "Default")
      (node (ref "LED4") (pin "C") (pinfunction "C_C") (pintype "passive"))
      (node (ref "Q4") (pin "3") (pinfunction "D_3") (pintype "passive"))
    )
    (net (code "46") (name "/LED4_G") (class "Default")
      (node (ref "JP58") (pin "1") (pinfunction "1_1") (pintype "passive"))
      (node (ref "Q4") (pin "1") (pinfunction "G_1") (pintype "passive"))
    )
    (net (code "47") (name "/LED5_A") (class "Default")
      (node (ref "LED5") (pin "A") (pinfunction "A_A") (pintype "passive"))
      (node (ref "R7") (pin "1") (pinfunction "1_1") (pintype "passive"))
    )
    (net (code "48") (name "/LED5_C") (class "Default")
      (node (ref "LED5") (pin "C") (pinfunction "C_C") (pintype "passive"))
      (node (ref "Q5") (pin "3") (pinfunction "D_3") (pintype "passive"))
    )
    (net (code "49") (name "/LED5_G") (class "Default")
      (node (ref "JP59") (pin "1") (pinfunction "1_1") (pintype "passive"))
      (node (ref "Q5") (pin "1") (pinfunction "G_1") (pintype "passive"))
    )
    (net (code "50") (name "/LED6_A") (class "Default")
      (node (ref "LED6") (pin "A") (pinfunction "A_A") (pintype "passive"))
      (node (ref "R8") (pin "1") (pinfunction "1_1") (pintype "passive"))
    )
    (net (code "51") (name "/LED6_C") (class "Default")
      (node (ref "LED6") (pin "C") (pinfunction "C_C") (pintype "passive"))
      (node (ref "Q6") (pin "3") (pinfunction "D_3") (pintype "passive"))
    )
    (net (code "52") (name "/LED6_G") (class "Default")
      (node (ref "JP60") (pin "1") (pinfunction "1_1") (pintype "passive"))
      (node (ref "Q6") (pin "1") (pinfunction "G_1") (pintype "passive"))
    )
    (net (code "53") (name "/LED7_A") (class "Default")
      (node (ref "LED7") (pin "A") (pinfunction "A_A") (pintype "passive"))
      (node (ref "R9") (pin "1") (pinfunction "1_1") (pintype "passive"))
    )
    (net (code "54") (name "/LED7_C") (class "Default")
      (node (ref "LED7") (pin "C") (pinfunction "C_C") (pintype "passive"))
      (node (ref "Q7") (pin "3") (pinfunction "D_3") (pintype "passive"))
    )
    (net (code "55") (name "/LED7_G") (class "Default")
      (node (ref "JP61") (pin "1") (pinfunction "1_1") (pintype "passive"))
      (node (ref "Q7") (pin "1") (pinfunction "G_1") (pintype "passive"))
    )
    (net (code "56") (name "/LED8_A") (class "Default")
      (node (ref "LED8") (pin "A") (pinfunction "A_A") (pintype "passive"))
      (node (ref "R10") (pin "1") (pinfunction "1_1") (pintype "passive"))
    )
    (net (code "57") (name "/LED8_C") (class "Default")
      (node (ref "LED8") (pin "C") (pinfunction "C_C") (pintype "passive"))
      (node (ref "Q8") (pin "3") (pinfunction "D_3") (pintype "passive"))
    )
    (net (code "58") (name "/LED8_G") (class "Default")
      (node (ref "JP62") (pin "1") (pinfunction "1_1") (pintype "passive"))
      (node (ref "Q8") (pin "1") (pinfunction "G_1") (pintype "passive"))
    )
    (net (code "59") (name "/LED9_A") (class "Default")
      (node (ref "LED9") (pin "A") (pinfunction "A_A") (pintype "passive"))
      (node (ref "R11") (pin "1") (pinfunction "1_1") (pintype "passive"))
    )
    (net (code "60") (name "/LED9_C") (class "Default")
      (node (ref "LED9") (pin "C") (pinfunction "C_C") (pintype "passive"))
      (node (ref "Q9") (pin "3") (pinfunction "D_3") (pintype "passive"))
    )
    (net (code "61") (name "/LED9_G") (class "Default")
      (node (ref "JP63") (pin "1") (pinfunction "1_1") (pintype "passive"))
      (node (ref "Q9") (pin "1") (pinfunction "G_1") (pintype "passive"))
    )
    (net (code "62") (name "/LED10_A") (class "Default")
      (node (ref "LED10") (pin "A") (pinfunction "A_A") (pintype "passive"))
      (node (ref "R12") (pin "1") (pinfunction "1_1") (pintype "passive"))
    )
    (net (code "63") (name "/LED10_C") (class "Default")
      (node (ref "LED10") (pin "C") (pinfunction "C_C") (pintype "passive"))
      (node (ref "Q10") (pin "3") (pinfunction "D_3") (pintype "passive"))
    )
    (net (code "64") (name "/LED10_G") (class "Default")
      (node (ref "JP64") (pin "1") (pinfunction "1_1") (pintype "passive"))
      (node (ref "Q10") (pin "1") (pinfunction "G_1") (pintype "passive"))
    )
    (net (code "65") (name "/LED11_A") (class "Default")
      (node (ref "LED11") (pin "A") (pinfunction "A_A") (pintype "passive"))
      (node (ref "R13") (pin "1") (pinfunction "1_1") (pintype "passive"))
    )
    (net (code "66") (name "/LED11_C") (class "Default")
      (node (ref "LED11") (pin "C") (pinfunction "C_C") (pintype "passive"))
      (node (ref "Q11") (pin "3") (pinfunction "D_3") (pintype "passive"))
    )
    (net (code "67") (name "/LED11_G") (class "Default")
      (node (ref "JP65") (pin "1") (pinfunction "1_1") (pintype "passive"))
      (node (ref "Q11") (pin "1") (pinfunction "G_1") (pintype "passive"))
    )
    (net (code "68") (name "/LED12_A") (class "Default")
      (node (ref "LED12") (pin "A") (pinfunction "A_A") (pintype "passive"))
      (node (ref "R20") (pin "1") (pinfunction "1_1") (pintype "passive"))
    )
    (net (code "69") (name "/LED12_C") (class "Default")
      (node (ref "LED12") (pin "C") (pinfunction "C_C") (pintype "passive"))
      (node (ref "Q12") (pin "3") (pinfunction "D_3") (pintype "passive"))
    )
    (net (code "70") (name "/LED12_G") (class "Default")
      (node (ref "JP71") (pin "1") (pinfunction "1_1") (pintype "passive"))
      (node (ref "Q12") (pin "1") (pinfunction "G_1") (pintype "passive"))
    )
    (net (code "71") (name "/LED13_R") (class "Default")
      (node (ref "LED13") (pin "A") (pinfunction "A_A") (pintype "passive"))
      (node (ref "R21") (pin "1") (pinfunction "1_1") (pintype "passive"))
    )
    (net (code "72") (name "/LED14_R") (class "Default")
      (node (ref "LED14") (pin "A") (pinfunction "A_A") (pintype "passive"))
      (node (ref "R22") (pin "1") (pinfunction "1_1") (pintype "passive"))
    )
    (net (code "73") (name "/LED15_R") (class "Default")
      (node (ref "LED15") (pin "A") (pinfunction "A_A") (pintype "passive"))
      (node (ref "R23") (pin "1") (pinfunction "1_1") (pintype "passive"))
    )
    (net (code "74") (name "/MCU_BOOT0") (class "Default")
      (node (ref "R15") (pin "1") (pinfunction "1_1") (pintype "passive"))
      (node (ref "R17") (pin "2") (pinfunction "2_2") (pintype "passive"))
      (node (ref "U1") (pin "60") (pinfunction "BOOT0_60") (pintype "bidirectional"))
    )
    (net (code "75") (name "/MCU_BOOT1") (class "Default")
      (node (ref "JP19") (pin "1") (pinfunction "1_1") (pintype "passive"))
      (node (ref "R16") (pin "1") (pinfunction "1_1") (pintype "passive"))
      (node (ref "R18") (pin "2") (pinfunction "2_2") (pintype "passive"))
    )
    (net (code "76") (name "/MCU_NRST") (class "Default")
      (node (ref "C8") (pin "1") (pinfunction "1_1") (pintype "passive"))
      (node (ref "JP69") (pin "2") (pinfunction "2_2") (pintype "passive"))
      (node (ref "R14") (pin "1") (pinfunction "1_1") (pintype "passive"))
      (node (ref "S1") (pin "1") (pinfunction "S_1") (pintype "passive"))
      (node (ref "S1") (pin "2") (pinfunction "S1_2") (pintype "passive"))
      (node (ref "U1") (pin "7") (pinfunction "NRST_7") (pintype "bidirectional"))
    )
    (net (code "77") (name "/MCU_PA0") (class "Default")
      (node (ref "JP1") (pin "2") (pinfunction "2_2") (pintype "passive"))
      (node (ref "U1") (pin "14") (pinfunction "PA0-WKUP_14") (pintype "bidirectional"))
    )
    (net (code "78") (name "/MCU_PA1") (class "Default")
      (node (ref "JP2") (pin "2") (pinfunction "2_2") (pintype "passive"))
      (node (ref "U1") (pin "15") (pinfunction "PA1_15") (pintype "bidirectional"))
    )
    (net (code "79") (name "/MCU_PA2") (class "Default")
      (node (ref "JP3") (pin "2") (pinfunction "2_2") (pintype "passive"))
      (node (ref "U1") (pin "16") (pinfunction "PA2_16") (pintype "bidirectional"))
    )
    (net (code "80") (name "/MCU_PA3") (class "Default")
      (node (ref "JP4") (pin "2") (pinfunction "2_2") (pintype "passive"))
      (node (ref "U1") (pin "17") (pinfunction "PA3_17") (pintype "bidirectional"))
    )
    (net (code "81") (name "/MCU_PA4") (class "Default")
      (node (ref "JP5") (pin "2") (pinfunction "2_2") (pintype "passive"))
      (node (ref "U1") (pin "20") (pinfunction "PA4_20") (pintype "bidirectional"))
    )
    (net (code "82") (name "/MCU_PA5") (class "Default")
      (node (ref "JP6") (pin "2") (pinfunction "2_2") (pintype "passive"))
      (node (ref "U1") (pin "21") (pinfunction "PA5_21") (pintype "bidirectional"))
    )
    (net (code "83") (name "/MCU_PA6") (class "Default")
      (node (ref "JP7") (pin "2") (pinfunction "2_2") (pintype "passive"))
      (node (ref "U1") (pin "22") (pinfunction "PA6_22") (pintype "bidirectional"))
    )
    (net (code "84") (name "/MCU_PA7") (class "Default")
      (node (ref "JP8") (pin "2") (pinfunction "2_2") (pintype "passive"))
      (node (ref "U1") (pin "23") (pinfunction "PA7_23") (pintype "bidirectional"))
    )
    (net (code "85") (name "/MCU_PA8") (class "Default")
      (node (ref "JP9") (pin "2") (pinfunction "2_2") (pintype "passive"))
      (node (ref "U1") (pin "41") (pinfunction "PA8_41") (pintype "bidirectional"))
    )
    (net (code "86") (name "/MCU_PA9") (class "Default")
      (node (ref "JP10") (pin "2") (pinfunction "2_2") (pintype "passive"))
      (node (ref "U1") (pin "42") (pinfunction "PA9_42") (pintype "bidirectional"))
    )
    (net (code "87") (name "/MCU_PA10") (class "Default")
      (node (ref "JP11") (pin "2") (pinfunction "2_2") (pintype "passive"))
      (node (ref "U1") (pin "43") (pinfunction "PA10_43") (pintype "bidirectional"))
    )
    (net (code "88") (name "/MCU_PA11") (class "Default")
      (node (ref "JP12") (pin "2") (pinfunction "2_2") (pintype "passive"))
      (node (ref "U1") (pin "44") (pinfunction "PA11_44") (pintype "bidirectional"))
    )
    (net (code "89") (name "/MCU_PA12") (class "Default")
      (node (ref "JP13") (pin "2") (pinfunction "2_2") (pintype "passive"))
      (node (ref "U1") (pin "45") (pinfunction "PA12_45") (pintype "bidirectional"))
    )
    (net (code "90") (name "/MCU_PA13") (class "Default")
      (node (ref "JP14") (pin "2") (pinfunction "2_2") (pintype "passive"))
      (node (ref "U1") (pin "46") (pinfunction "PA13_46") (pintype "bidirectional"))
    )
    (net (code "91") (name "/MCU_PA14") (class "Default")
      (node (ref "JP15") (pin "2") (pinfunction "2_2") (pintype "passive"))
      (node (ref "U1") (pin "49") (pinfunction "PA14_49") (pintype "bidirectional"))
    )
    (net (code "92") (name "/MCU_PA15") (class "Default")
      (node (ref "JP16") (pin "2") (pinfunction "2_2") (pintype "passive"))
      (node (ref "U1") (pin "50") (pinfunction "PA15_50") (pintype "bidirectional"))
    )
    (net (code "93") (name "/MCU_PB0") (class "Default")
      (node (ref "JP17") (pin "2") (pinfunction "2_2") (pintype "passive"))
      (node (ref "U1") (pin "26") (pinfunction "PB0_26") (pintype "bidirectional"))
    )
    (net (code "94") (name "/MCU_PB1") (class "Default")
      (node (ref "JP18") (pin "2") (pinfunction "2_2") (pintype "passive"))
      (node (ref "U1") (pin "27") (pinfunction "PB1_27") (pintype "bidirectional"))
    )
    (net (code "95") (name "/MCU_PB2") (class "Default")
      (node (ref "JP19") (pin "2") (pinfunction "2_2") (pintype "passive"))
      (node (ref "U1") (pin "28") (pinfunction "PB2_28") (pintype "bidirectional"))
    )
    (net (code "96") (name "/MCU_PB3") (class "Default")
      (node (ref "JP20") (pin "2") (pinfunction "2_2") (pintype "passive"))
      (node (ref "U1") (pin "55") (pinfunction "PB3_55") (pintype "bidirectional"))
    )
    (net (code "97") (name "/MCU_PB4") (class "Default")
      (node (ref "JP21") (pin "2") (pinfunction "2_2") (pintype "passive"))
      (node (ref "U1") (pin "56") (pinfunction "PB4_56") (pintype "bidirectional"))
    )
    (net (code "98") (name "/MCU_PB5") (class "Default")
      (node (ref "JP22") (pin "2") (pinfunction "2_2") (pintype "passive"))
      (node (ref "U1") (pin "57") (pinfunction "PB5_57") (pintype "bidirectional"))
    )
    (net (code "99") (name "/MCU_PB6") (class "Default")
      (node (ref "JP23") (pin "2") (pinfunction "2_2") (pintype "passive"))
      (node (ref "U1") (pin "58") (pinfunction "PB6_58") (pintype "bidirectional"))
    )
    (net (code "100") (name "/MCU_PB7") (class "Default")
      (node (ref "JP24") (pin "2") (pinfunction "2_2") (pintype "passive"))
      (node (ref "U1") (pin "59") (pinfunction "PB7_59") (pintype "bidirectional"))
    )
    (net (code "101") (name "/MCU_PB8") (class "Default")
      (node (ref "JP25") (pin "2") (pinfunction "2_2") (pintype "passive"))
      (node (ref "U1") (pin "61") (pinfunction "PB8_61") (pintype "bidirectional"))
    )
    (net (code "102") (name "/MCU_PB9") (class "Default")
      (node (ref "JP26") (pin "2") (pinfunction "2_2") (pintype "passive"))
      (node (ref "U1") (pin "62") (pinfunction "PB9_62") (pintype "bidirectional"))
    )
    (net (code "103") (name "/MCU_PB10") (class "Default")
      (node (ref "JP27") (pin "2") (pinfunction "2_2") (pintype "passive"))
      (node (ref "U1") (pin "29") (pinfunction "PB10_29") (pintype "bidirectional"))
    )
    (net (code "104") (name "/MCU_PB11") (class "Default")
      (node (ref "JP28") (pin "2") (pinfunction "2_2") (pintype "passive"))
      (node (ref "U1") (pin "30") (pinfunction "PB11_30") (pintype "bidirectional"))
    )
    (net (code "105") (name "/MCU_PB12") (class "Default")
      (node (ref "JP29") (pin "2") (pinfunction "2_2") (pintype "passive"))
      (node (ref "U1") (pin "33") (pinfunction "PB12_33") (pintype "bidirectional"))
    )
    (net (code "106") (name "/MCU_PB13") (class "Default")
      (node (ref "JP30") (pin "2") (pinfunction "2_2") (pintype "passive"))
      (node (ref "U1") (pin "34") (pinfunction "PB13_34") (pintype "bidirectional"))
    )
    (net (code "107") (name "/MCU_PB14") (class "Default")
      (node (ref "JP31") (pin "2") (pinfunction "2_2") (pintype "passive"))
      (node (ref "U1") (pin "35") (pinfunction "PB14_35") (pintype "bidirectional"))
    )
    (net (code "108") (name "/MCU_PB15") (class "Default")
      (node (ref "JP32") (pin "2") (pinfunction "2_2") (pintype "passive"))
      (node (ref "U1") (pin "36") (pinfunction "PB15_36") (pintype "bidirectional"))
    )
    (net (code "109") (name "/MCU_PC0") (class "Default")
      (node (ref "JP33") (pin "1") (pinfunction "1_1") (pintype "passive"))
      (node (ref "U1") (pin "8") (pinfunction "PC0_8") (pintype "bidirectional"))
    )
    (net (code "110") (name "/MCU_PC1") (class "Default")
      (node (ref "JP34") (pin "1") (pinfunction "1_1") (pintype "passive"))
      (node (ref "U1") (pin "9") (pinfunction "PC1_9") (pintype "bidirectional"))
    )
    (net (code "111") (name "/MCU_PC2") (class "Default")
      (node (ref "JP35") (pin "1") (pinfunction "1_1") (pintype "passive"))
      (node (ref "U1") (pin "10") (pinfunction "PC2_10") (pintype "bidirectional"))
    )
    (net (code "112") (name "/MCU_PC3") (class "Default")
      (node (ref "JP36") (pin "1") (pinfunction "1_1") (pintype "passive"))
      (node (ref "U1") (pin "11") (pinfunction "PC3_11") (pintype "bidirectional"))
    )
    (net (code "113") (name "/MCU_PC4") (class "Default")
      (node (ref "JP37") (pin "1") (pinfunction "1_1") (pintype "passive"))
      (node (ref "U1") (pin "24") (pinfunction "PC4_24") (pintype "bidirectional"))
    )
    (net (code "114") (name "/MCU_PC5") (class "Default")
      (node (ref "JP38") (pin "1") (pinfunction "1_1") (pintype "passive"))
      (node (ref "U1") (pin "25") (pinfunction "PC5_25") (pintype "bidirectional"))
    )
    (net (code "115") (name "/MCU_PC6") (class "Default")
      (node (ref "JP39") (pin "1") (pinfunction "1_1") (pintype "passive"))
      (node (ref "U1") (pin "37") (pinfunction "PC6_37") (pintype "bidirectional"))
    )
    (net (code "116") (name "/MCU_PC7") (class "Default")
      (node (ref "JP40") (pin "1") (pinfunction "1_1") (pintype "passive"))
      (node (ref "U1") (pin "38") (pinfunction "PC7_38") (pintype "bidirectional"))
    )
    (net (code "117") (name "/MCU_PC8") (class "Default")
      (node (ref "JP41") (pin "1") (pinfunction "1_1") (pintype "passive"))
      (node (ref "U1") (pin "39") (pinfunction "PC8_39") (pintype "bidirectional"))
    )
    (net (code "118") (name "/MCU_PC9") (class "Default")
      (node (ref "JP42") (pin "1") (pinfunction "1_1") (pintype "passive"))
      (node (ref "U1") (pin "40") (pinfunction "PC9_40") (pintype "bidirectional"))
    )
    (net (code "119") (name "/MCU_PC10") (class "Default")
      (node (ref "JP43") (pin "1") (pinfunction "1_1") (pintype "passive"))
      (node (ref "U1") (pin "51") (pinfunction "PC10_51") (pintype "bidirectional"))
    )
    (net (code "120") (name "/MCU_PC11") (class "Default")
      (node (ref "JP44") (pin "1") (pinfunction "1_1") (pintype "passive"))
      (node (ref "U1") (pin "52") (pinfunction "PC11_52") (pintype "bidirectional"))
    )
    (net (code "121") (name "/MCU_PC12") (class "Default")
      (node (ref "JP45") (pin "1") (pinfunction "1_1") (pintype "passive"))
      (node (ref "U1") (pin "53") (pinfunction "PC12_53") (pintype "bidirectional"))
    )
    (net (code "122") (name "/MCU_PC13") (class "Default")
      (node (ref "JP46") (pin "1") (pinfunction "1_1") (pintype "passive"))
      (node (ref "U1") (pin "2") (pinfunction "PC13-RTC_AF1_2") (pintype "bidirectional"))
    )
    (net (code "123") (name "/MCU_PC14") (class "Default")
      (node (ref "JP47") (pin "1") (pinfunction "1_1") (pintype "passive"))
      (node (ref "U1") (pin "3") (pinfunction "PC14-OSC32_IN_3") (pintype "bidirectional"))
    )
    (net (code "124") (name "/MCU_PC15") (class "Default")
      (node (ref "JP48") (pin "1") (pinfunction "1_1") (pintype "passive"))
      (node (ref "U1") (pin "4") (pinfunction "PC15-OSC32_OUT_4") (pintype "bidirectional"))
    )
    (net (code "125") (name "/MCU_PD2") (class "Default")
      (node (ref "JP49") (pin "1") (pinfunction "1_1") (pintype "passive"))
      (node (ref "U1") (pin "54") (pinfunction "PD2_54") (pintype "bidirectional"))
    )
    (net (code "126") (name "/MCU_PH0") (class "Default")
      (node (ref "QG1") (pin "3") (pinfunction "OUT_3") (pintype "output"))
      (node (ref "U1") (pin "5") (pinfunction "PH0-OSC_IN_5") (pintype "bidirectional"))
    )
    (net (code "127") (name "/MCU_PH1") (class "Default")
      (node (ref "JP70") (pin "1") (pinfunction "1_1") (pintype "passive"))
      (node (ref "U1") (pin "6") (pinfunction "PH1-OSC_OUT_6") (pintype "bidirectional"))
    )
    (net (code "128") (name "/MCU_VCAP_1") (class "Default")
      (node (ref "C21") (pin "1") (pinfunction "1_1") (pintype "passive"))
      (node (ref "U1") (pin "31") (pinfunction "VCAP_1_31") (pintype "bidirectional"))
    )
    (net (code "129") (name "/MCU_VCAP_2") (class "Default")
      (node (ref "C20") (pin "1") (pinfunction "1_1") (pintype "passive"))
      (node (ref "U1") (pin "47") (pinfunction "VCAP_2_47") (pintype "bidirectional"))
    )
    (net (code "130") (name "/OLYMPUS_GPIO1") (class "Default")
      (node (ref "JP5") (pin "1") (pinfunction "1_1") (pintype "passive"))
      (node (ref "JP55") (pin "2") (pinfunction "2_2") (pintype "passive"))
    )
    (net (code "131") (name "/OLYMPUS_GPIO2") (class "Default")
      (node (ref "JP56") (pin "2") (pinfunction "2_2") (pintype "passive"))
      (node (ref "JP6") (pin "1") (pinfunction "1_1") (pintype "passive"))
    )
    (net (code "132") (name "/OLYMPUS_GPIO3") (class "Default")
      (node (ref "JP57") (pin "2") (pinfunction "2_2") (pintype "passive"))
      (node (ref "JP8") (pin "1") (pinfunction "1_1") (pintype "passive"))
    )
    (net (code "133") (name "/OLYMPUS_GPIO4") (class "Default")
      (node (ref "JP20") (pin "1") (pinfunction "1_1") (pintype "passive"))
      (node (ref "JP58") (pin "2") (pinfunction "2_2") (pintype "passive"))
      (node (ref "JP67") (pin "2") (pinfunction "2_2") (pintype "passive"))
    )
    (net (code "134") (name "/OLYMPUS_GPIO5") (class "Default")
      (node (ref "JP21") (pin "1") (pinfunction "1_1") (pintype "passive"))
      (node (ref "JP59") (pin "2") (pinfunction "2_2") (pintype "passive"))
    )
    (net (code "135") (name "/OLYMPUS_GPIO6") (class "Default")
      (node (ref "JP22") (pin "1") (pinfunction "1_1") (pintype "passive"))
      (node (ref "JP60") (pin "2") (pinfunction "2_2") (pintype "passive"))
    )
    (net (code "136") (name "/OLYMPUS_GPIO7") (class "Default")
      (node (ref "JP37") (pin "2") (pinfunction "2_2") (pintype "passive"))
      (node (ref "JP61") (pin "2") (pinfunction "2_2") (pintype "passive"))
    )
    (net (code "137") (name "/OLYMPUS_GPIO8") (class "Default")
      (node (ref "JP38") (pin "2") (pinfunction "2_2") (pintype "passive"))
      (node (ref "JP62") (pin "2") (pinfunction "2_2") (pintype "passive"))
    )
    (net (code "138") (name "/OLYMPUS_GPIO9") (class "Default")
      (node (ref "JP40") (pin "2") (pinfunction "2_2") (pintype "passive"))
      (node (ref "JP63") (pin "2") (pinfunction "2_2") (pintype "passive"))
    )
    (net (code "139") (name "/OLYMPUS_GPIO10") (class "Default")
      (node (ref "JP41") (pin "2") (pinfunction "2_2") (pintype "passive"))
      (node (ref "JP64") (pin "2") (pinfunction "2_2") (pintype "passive"))
    )
    (net (code "140") (name "/OLYMPUS_GPIO11") (class "Default")
      (node (ref "JP49") (pin "2") (pinfunction "2_2") (pintype "passive"))
      (node (ref "JP65") (pin "2") (pinfunction "2_2") (pintype "passive"))
    )
    (net (code "141") (name "/OLYMPUS_GPIO12") (class "Default")
      (node (ref "JP70") (pin "2") (pinfunction "2_2") (pintype "passive"))
      (node (ref "JP71") (pin "2") (pinfunction "2_2") (pintype "passive"))
    )
    (net (code "142") (name "/OLYMPUS_SWDCLK") (class "Default")
      (node (ref "J1") (pin "4") (pinfunction "4_4") (pintype "bidirectional"))
      (node (ref "JP15") (pin "1") (pinfunction "1_1") (pintype "passive"))
    )
    (net (code "143") (name "/OLYMPUS_SWDIO") (class "Default")
      (node (ref "J1") (pin "2") (pinfunction "2_2") (pintype "bidirectional"))
      (node (ref "JP14") (pin "1") (pinfunction "1_1") (pintype "passive"))
    )
    (net (code "144") (name "/OLYMPUS_USBDN") (class "Default")
      (node (ref "JP12") (pin "1") (pinfunction "1_1") (pintype "passive"))
      (node (ref "X1") (pin "2") (pinfunction "2_2") (pintype "input"))
    )
    (net (code "145") (name "/OLYMPUS_USBDP") (class "Default")
      (node (ref "JP13") (pin "1") (pinfunction "1_1") (pintype "passive"))
      (node (ref "X1") (pin "3") (pinfunction "3_3") (pintype "input"))
    )
    (net (code "146") (name "/OLYMPUS_USBID") (class "Default")
      (node (ref "JP11") (pin "1") (pinfunction "1_1") (pintype "passive"))
      (node (ref "X1") (pin "4") (pinfunction "4_4") (pintype "input"))
    )
    (net (code "147") (name "/OSC_EN") (class "Default")
      (node (ref "QG1") (pin "1") (pinfunction "E/D_1") (pintype "input"))
      (node (ref "R19") (pin "1") (pinfunction "1_1") (pintype "passive"))
    )
    (net (code "148") (name "/PP3V3") (class "Default")
      (node (ref "C1") (pin "1") (pinfunction "1_1") (pintype "passive"))
      (node (ref "C2") (pin "1") (pinfunction "1_1") (pintype "passive"))
      (node (ref "C3") (pin "1") (pinfunction "1_1") (pintype "passive"))
      (node (ref "C4") (pin "1") (pinfunction "1_1") (pintype "passive"))
      (node (ref "C5") (pin "1") (pinfunction "1_1") (pintype "passive"))
      (node (ref "C9") (pin "1") (pinfunction "1_1") (pintype "passive"))
      (node (ref "JP52") (pin "1") (pinfunction "1_1") (pintype "passive"))
      (node (ref "JP66") (pin "1") (pinfunction "1_1") (pintype "passive"))
      (node (ref "L1") (pin "2") (pinfunction "2_2") (pintype "passive"))
      (node (ref "QG1") (pin "4") (pinfunction "VCC_4") (pintype "power_in"))
      (node (ref "R1") (pin "2") (pinfunction "2_2") (pintype "passive"))
      (node (ref "R14") (pin "2") (pinfunction "2_2") (pintype "passive"))
      (node (ref "R15") (pin "2") (pinfunction "2_2") (pintype "passive"))
      (node (ref "R16") (pin "2") (pinfunction "2_2") (pintype "passive"))
      (node (ref "R19") (pin "2") (pinfunction "2_2") (pintype "passive"))
      (node (ref "R2") (pin "2") (pinfunction "2_2") (pintype "passive"))
      (node (ref "R21") (pin "2") (pinfunction "2_2") (pintype "passive"))
      (node (ref "SV1") (pin "3") (pinfunction "3_3") (pintype "passive"))
      (node (ref "SV11") (pin "3") (pinfunction "3_3") (pintype "passive"))
      (node (ref "SV13") (pin "3") (pinfunction "3_3") (pintype "passive"))
      (node (ref "SV15") (pin "3") (pinfunction "3_3") (pintype "passive"))
      (node (ref "SV3") (pin "3") (pinfunction "3_3") (pintype "passive"))
      (node (ref "SV5") (pin "3") (pinfunction "3_3") (pintype "passive"))
      (node (ref "SV7") (pin "3") (pinfunction "3_3") (pintype "passive"))
      (node (ref "SV9") (pin "3") (pinfunction "3_3") (pintype "passive"))
      (node (ref "U1") (pin "19") (pinfunction "VDD_19") (pintype "bidirectional"))
      (node (ref "U1") (pin "32") (pinfunction "VDD_32") (pintype "bidirectional"))
      (node (ref "U1") (pin "48") (pinfunction "VDD_48") (pintype "bidirectional"))
      (node (ref "U1") (pin "64") (pinfunction "VDD_64") (pintype "bidirectional"))
    )
    (net (code "149") (name "/PP3V3A") (class "Default")
      (node (ref "C6") (pin "1") (pinfunction "1_1") (pintype "passive"))
      (node (ref "C7") (pin "1") (pinfunction "1_1") (pintype "passive"))
      (node (ref "L1") (pin "1") (pinfunction "1_1") (pintype "passive"))
      (node (ref "U1") (pin "13") (pinfunction "VDDA_13") (pintype "bidirectional"))
    )
    (net (code "150") (name "/PP5V") (class "Default")
      (node (ref "JP51") (pin "1") (pinfunction "1_1") (pintype "passive"))
      (node (ref "R10") (pin "2") (pinfunction "2_2") (pintype "passive"))
      (node (ref "R11") (pin "2") (pinfunction "2_2") (pintype "passive"))
      (node (ref "R12") (pin "2") (pinfunction "2_2") (pintype "passive"))
      (node (ref "R13") (pin "2") (pinfunction "2_2") (pintype "passive"))
      (node (ref "R20") (pin "2") (pinfunction "2_2") (pintype "passive"))
      (node (ref "R22") (pin "2") (pinfunction "2_2") (pintype "passive"))
      (node (ref "R3") (pin "2") (pinfunction "2_2") (pintype "passive"))
      (node (ref "R4") (pin "2") (pinfunction "2_2") (pintype "passive"))
      (node (ref "R5") (pin "2") (pinfunction "2_2") (pintype "passive"))
      (node (ref "R6") (pin "2") (pinfunction "2_2") (pintype "passive"))
      (node (ref "R7") (pin "2") (pinfunction "2_2") (pintype "passive"))
      (node (ref "R8") (pin "2") (pinfunction "2_2") (pintype "passive"))
      (node (ref "R9") (pin "2") (pinfunction "2_2") (pintype "passive"))
      (node (ref "SV1") (pin "2") (pinfunction "2_2") (pintype "passive"))
      (node (ref "SV11") (pin "2") (pinfunction "2_2") (pintype "passive"))
      (node (ref "SV13") (pin "2") (pinfunction "2_2") (pintype "passive"))
      (node (ref "SV15") (pin "2") (pinfunction "2_2") (pintype "passive"))
      (node (ref "SV3") (pin "2") (pinfunction "2_2") (pintype "passive"))
      (node (ref "SV5") (pin "2") (pinfunction "2_2") (pintype "passive"))
      (node (ref "SV7") (pin "2") (pinfunction "2_2") (pintype "passive"))
      (node (ref "SV9") (pin "2") (pinfunction "2_2") (pintype "passive"))
    )
    (net (code "151") (name "/PP12V") (class "Default")
      (node (ref "JP50") (pin "1") (pinfunction "1_1") (pintype "passive"))
      (node (ref "R23") (pin "2") (pinfunction "2_2") (pintype "passive"))
      (node (ref "SV1") (pin "1") (pinfunction "1_1") (pintype "passive"))
      (node (ref "SV11") (pin "1") (pinfunction "1_1") (pintype "passive"))
      (node (ref "SV13") (pin "1") (pinfunction "1_1") (pintype "passive"))
      (node (ref "SV15") (pin "1") (pinfunction "1_1") (pintype "passive"))
      (node (ref "SV3") (pin "1") (pinfunction "1_1") (pintype "passive"))
      (node (ref "SV5") (pin "1") (pinfunction "1_1") (pintype "passive"))
      (node (ref "SV7") (pin "1") (pinfunction "1_1") (pintype "passive"))
      (node (ref "SV9") (pin "1") (pinfunction "1_1") (pintype "passive"))
    )
    (net (code "152") (name "/ZEUS_GPIO") (class "Default")
      (node (ref "JP44") (pin "2") (pinfunction "2_2") (pintype "passive"))
      (node (ref "SV1") (pin "8") (pinfunction "8_8") (pintype "passive"))
    )
    (net (code "153") (name "/ZEUS_SHUTDOWN_N") (class "Default")
      (node (ref "JP10") (pin "1") (pinfunction "1_1") (pintype "passive"))
      (node (ref "SV1") (pin "7") (pinfunction "7_7") (pintype "passive"))
    )
    (net (code "154") (name "GND") (class "Default")
      (node (ref "C1") (pin "2") (pinfunction "2_2") (pintype "passive"))
      (node (ref "C2") (pin "2") (pinfunction "2_2") (pintype "passive"))
      (node (ref "C20") (pin "2") (pinfunction "2_2") (pintype "passive"))
      (node (ref "C21") (pin "2") (pinfunction "2_2") (pintype "passive"))
      (node (ref "C3") (pin "2") (pinfunction "2_2") (pintype "passive"))
      (node (ref "C4") (pin "2") (pinfunction "2_2") (pintype "passive"))
      (node (ref "C5") (pin "2") (pinfunction "2_2") (pintype "passive"))
      (node (ref "C6") (pin "2") (pinfunction "2_2") (pintype "passive"))
      (node (ref "C7") (pin "2") (pinfunction "2_2") (pintype "passive"))
      (node (ref "C8") (pin "2") (pinfunction "2_2") (pintype "passive"))
      (node (ref "C9") (pin "2") (pinfunction "2_2") (pintype "passive"))
      (node (ref "J1") (pin "3") (pinfunction "3_3") (pintype "bidirectional"))
      (node (ref "J1") (pin "5") (pinfunction "5_5") (pintype "bidirectional"))
      (node (ref "JP50") (pin "2") (pinfunction "2_2") (pintype "passive"))
      (node (ref "JP51") (pin "2") (pinfunction "2_2") (pintype "passive"))
      (node (ref "JP52") (pin "2") (pinfunction "2_2") (pintype "passive"))
      (node (ref "JP53") (pin "2") (pinfunction "2_2") (pintype "passive"))
      (node (ref "JP54") (pin "2") (pinfunction "2_2") (pintype "passive"))
      (node (ref "LED13") (pin "C") (pinfunction "C_C") (pintype "passive"))
      (node (ref "LED14") (pin "C") (pinfunction "C_C") (pintype "passive"))
      (node (ref "LED15") (pin "C") (pinfunction "C_C") (pintype "passive"))
      (node (ref "Q1") (pin "2") (pinfunction "S_2") (pintype "passive"))
      (node (ref "Q10") (pin "2") (pinfunction "S_2") (pintype "passive"))
      (node (ref "Q11") (pin "2") (pinfunction "S_2") (pintype "passive"))
      (node (ref "Q12") (pin "2") (pinfunction "S_2") (pintype "passive"))
      (node (ref "Q2") (pin "2") (pinfunction "S_2") (pintype "passive"))
      (node (ref "Q3") (pin "2") (pinfunction "S_2") (pintype "passive"))
      (node (ref "Q4") (pin "2") (pinfunction "S_2") (pintype "passive"))
      (node (ref "Q5") (pin "2") (pinfunction "S_2") (pintype "passive"))
      (node (ref "Q6") (pin "2") (pinfunction "S_2") (pintype "passive"))
      (node (ref "Q7") (pin "2") (pinfunction "S_2") (pintype "passive"))
      (node (ref "Q8") (pin "2") (pinfunction "S_2") (pintype "passive"))
      (node (ref "Q9") (pin "2") (pinfunction "S_2") (pintype "passive"))
      (node (ref "QG1") (pin "2") (pinfunction "GND_2") (pintype "power_in"))
      (node (ref "R17") (pin "1") (pinfunction "1_1") (pintype "passive"))
      (node (ref "R18") (pin "1") (pinfunction "1_1") (pintype "passive"))
      (node (ref "S1") (pin "3") (pinfunction "P_3") (pintype "passive"))
      (node (ref "S1") (pin "4") (pinfunction "P1_4") (pintype "passive"))
      (node (ref "SV1") (pin "4") (pinfunction "4_4") (pintype "passive"))
      (node (ref "SV11") (pin "4") (pinfunction "4_4") (pintype "passive"))
      (node (ref "SV13") (pin "4") (pinfunction "4_4") (pintype "passive"))
      (node (ref "SV15") (pin "4") (pinfunction "4_4") (pintype "passive"))
      (node (ref "SV3") (pin "4") (pinfunction "4_4") (pintype "passive"))
      (node (ref "SV5") (pin "4") (pinfunction "4_4") (pintype "passive"))
      (node (ref "SV7") (pin "4") (pinfunction "4_4") (pintype "passive"))
      (node (ref "SV9") (pin "4") (pinfunction "4_4") (pintype "passive"))
      (node (ref "U1") (pin "12") (pinfunction "VSSA_12") (pintype "bidirectional"))
      (node (ref "U1") (pin "18") (pinfunction "VSS_18") (pintype "bidirectional"))
      (node (ref "U1") (pin "63") (pinfunction "VSS_63") (pintype "bidirectional"))
      (node (ref "X1") (pin "5") (pinfunction "5_5") (pintype "input"))
    )
    (net (code "155") (name "unconnected-(J1-Pad7)") (class "Default")
      (node (ref "J1") (pin "7") (pinfunction "7_7") (pintype "bidirectional"))
    )
    (net (code "156") (name "unconnected-(J1-Pad9)") (class "Default")
      (node (ref "J1") (pin "9") (pinfunction "9_9") (pintype "bidirectional"))
    )
    (net (code "157") (name "unconnected-(JP72-Pad1)") (class "Default")
      (node (ref "JP72") (pin "1") (pinfunction "1_1") (pintype "passive"))
    )
    (net (code "158") (name "unconnected-(JP73-Pad1)") (class "Default")
      (node (ref "JP73") (pin "1") (pinfunction "1_1") (pintype "passive"))
    )
    (net (code "159") (name "unconnected-(JP74-Pad1)") (class "Default")
      (node (ref "JP74") (pin "1") (pinfunction "1_1") (pintype "passive"))
    )
    (net (code "160") (name "unconnected-(JP75-Pad1)") (class "Default")
      (node (ref "JP75") (pin "1") (pinfunction "1_1") (pintype "passive"))
    )
    (net (code "161") (name "unconnected-(JP76-Pad1)") (class "Default")
      (node (ref "JP76") (pin "1") (pinfunction "1_1") (pintype "passive"))
    )
    (net (code "162") (name "unconnected-(JP77-Pad1)") (class "Default")
      (node (ref "JP77") (pin "1") (pinfunction "1_1") (pintype "passive"))
    )
    (net (code "163") (name "unconnected-(JP78-Pad1)") (class "Default")
      (node (ref "JP78") (pin "1") (pinfunction "1_1") (pintype "passive"))
    )
    (net (code "164") (name "unconnected-(JP79-Pad1)") (class "Default")
      (node (ref "JP79") (pin "1") (pinfunction "1_1") (pintype "passive"))
    )
    (net (code "165") (name "unconnected-(JP80-Pad1)") (class "Default")
      (node (ref "JP80") (pin "1") (pinfunction "1_1") (pintype "passive"))
    )
    (net (code "166") (name "unconnected-(JP81-Pad1)") (class "Default")
      (node (ref "JP81") (pin "1") (pinfunction "1_1") (pintype "passive"))
    )
    (net (code "167") (name "unconnected-(JP82-Pad1)") (class "Default")
      (node (ref "JP82") (pin "1") (pinfunction "1_1") (pintype "passive"))
    )
    (net (code "168") (name "unconnected-(JP83-Pad1)") (class "Default")
      (node (ref "JP83") (pin "1") (pinfunction "1_1") (pintype "passive"))
    )
    (net (code "169") (name "unconnected-(JP84-Pad1)") (class "Default")
      (node (ref "JP84") (pin "1") (pinfunction "1_1") (pintype "passive"))
    )
    (net (code "170") (name "unconnected-(JP85-Pad1)") (class "Default")
      (node (ref "JP85") (pin "1") (pinfunction "1_1") (pintype "passive"))
    )
    (net (code "171") (name "unconnected-(JP86-Pad1)") (class "Default")
      (node (ref "JP86") (pin "1") (pinfunction "1_1") (pintype "passive"))
    )
    (net (code "172") (name "unconnected-(JP87-Pad1)") (class "Default")
      (node (ref "JP87") (pin "1") (pinfunction "1_1") (pintype "passive"))
    )
    (net (code "173") (name "unconnected-(SV1-Pad9)") (class "Default")
      (node (ref "SV1") (pin "9") (pinfunction "9_9") (pintype "passive"))
    )
    (net (code "174") (name "unconnected-(SV1-Pad10)") (class "Default")
      (node (ref "SV1") (pin "10") (pinfunction "10_10") (pintype "passive"))
    )
    (net (code "175") (name "unconnected-(SV2-Pad1)") (class "Default")
      (node (ref "SV2") (pin "1") (pinfunction "1_1") (pintype "passive"))
    )
    (net (code "176") (name "unconnected-(SV2-Pad2)") (class "Default")
      (node (ref "SV2") (pin "2") (pinfunction "2_2") (pintype "passive"))
    )
    (net (code "177") (name "unconnected-(SV2-Pad3)") (class "Default")
      (node (ref "SV2") (pin "3") (pinfunction "3_3") (pintype "passive"))
    )
    (net (code "178") (name "unconnected-(SV2-Pad4)") (class "Default")
      (node (ref "SV2") (pin "4") (pinfunction "4_4") (pintype "passive"))
    )
    (net (code "179") (name "unconnected-(SV2-Pad5)") (class "Default")
      (node (ref "SV2") (pin "5") (pinfunction "5_5") (pintype "passive"))
    )
    (net (code "180") (name "unconnected-(SV2-Pad6)") (class "Default")
      (node (ref "SV2") (pin "6") (pinfunction "6_6") (pintype "passive"))
    )
    (net (code "181") (name "unconnected-(SV2-Pad7)") (class "Default")
      (node (ref "SV2") (pin "7") (pinfunction "7_7") (pintype "passive"))
    )
    (net (code "182") (name "unconnected-(SV2-Pad8)") (class "Default")
      (node (ref "SV2") (pin "8") (pinfunction "8_8") (pintype "passive"))
    )
    (net (code "183") (name "unconnected-(SV2-Pad9)") (class "Default")
      (node (ref "SV2") (pin "9") (pinfunction "9_9") (pintype "passive"))
    )
    (net (code "184") (name "unconnected-(SV2-Pad10)") (class "Default")
      (node (ref "SV2") (pin "10") (pinfunction "10_10") (pintype "passive"))
    )
    (net (code "185") (name "unconnected-(SV3-Pad9)") (class "Default")
      (node (ref "SV3") (pin "9") (pinfunction "9_9") (pintype "passive"))
    )
    (net (code "186") (name "unconnected-(SV3-Pad10)") (class "Default")
      (node (ref "SV3") (pin "10") (pinfunction "10_10") (pintype "passive"))
    )
    (net (code "187") (name "unconnected-(SV4-Pad1)") (class "Default")
      (node (ref "SV4") (pin "1") (pinfunction "1_1") (pintype "passive"))
    )
    (net (code "188") (name "unconnected-(SV4-Pad2)") (class "Default")
      (node (ref "SV4") (pin "2") (pinfunction "2_2") (pintype "passive"))
    )
    (net (code "189") (name "unconnected-(SV4-Pad3)") (class "Default")
      (node (ref "SV4") (pin "3") (pinfunction "3_3") (pintype "passive"))
    )
    (net (code "190") (name "unconnected-(SV4-Pad4)") (class "Default")
      (node (ref "SV4") (pin "4") (pinfunction "4_4") (pintype "passive"))
    )
    (net (code "191") (name "unconnected-(SV4-Pad5)") (class "Default")
      (node (ref "SV4") (pin "5") (pinfunction "5_5") (pintype "passive"))
    )
    (net (code "192") (name "unconnected-(SV4-Pad6)") (class "Default")
      (node (ref "SV4") (pin "6") (pinfunction "6_6") (pintype "passive"))
    )
    (net (code "193") (name "unconnected-(SV4-Pad7)") (class "Default")
      (node (ref "SV4") (pin "7") (pinfunction "7_7") (pintype "passive"))
    )
    (net (code "194") (name "unconnected-(SV4-Pad8)") (class "Default")
      (node (ref "SV4") (pin "8") (pinfunction "8_8") (pintype "passive"))
    )
    (net (code "195") (name "unconnected-(SV4-Pad9)") (class "Default")
      (node (ref "SV4") (pin "9") (pinfunction "9_9") (pintype "passive"))
    )
    (net (code "196") (name "unconnected-(SV4-Pad10)") (class "Default")
      (node (ref "SV4") (pin "10") (pinfunction "10_10") (pintype "passive"))
    )
    (net (code "197") (name "unconnected-(SV5-Pad10)") (class "Default")
      (node (ref "SV5") (pin "10") (pinfunction "10_10") (pintype "passive"))
    )
    (net (code "198") (name "unconnected-(SV6-Pad1)") (class "Default")
      (node (ref "SV6") (pin "1") (pinfunction "1_1") (pintype "passive"))
    )
    (net (code "199") (name "unconnected-(SV6-Pad2)") (class "Default")
      (node (ref "SV6") (pin "2") (pinfunction "2_2") (pintype "passive"))
    )
    (net (code "200") (name "unconnected-(SV6-Pad3)") (class "Default")
      (node (ref "SV6") (pin "3") (pinfunction "3_3") (pintype "passive"))
    )
    (net (code "201") (name "unconnected-(SV6-Pad4)") (class "Default")
      (node (ref "SV6") (pin "4") (pinfunction "4_4") (pintype "passive"))
    )
    (net (code "202") (name "unconnected-(SV6-Pad5)") (class "Default")
      (node (ref "SV6") (pin "5") (pinfunction "5_5") (pintype "passive"))
    )
    (net (code "203") (name "unconnected-(SV6-Pad6)") (class "Default")
      (node (ref "SV6") (pin "6") (pinfunction "6_6") (pintype "passive"))
    )
    (net (code "204") (name "unconnected-(SV6-Pad7)") (class "Default")
      (node (ref "SV6") (pin "7") (pinfunction "7_7") (pintype "passive"))
    )
    (net (code "205") (name "unconnected-(SV6-Pad8)") (class "Default")
      (node (ref "SV6") (pin "8") (pinfunction "8_8") (pintype "passive"))
    )
    (net (code "206") (name "unconnected-(SV6-Pad9)") (class "Default")
      (node (ref "SV6") (pin "9") (pinfunction "9_9") (pintype "passive"))
    )
    (net (code "207") (name "unconnected-(SV6-Pad10)") (class "Default")
      (node (ref "SV6") (pin "10") (pinfunction "10_10") (pintype "passive"))
    )
    (net (code "208") (name "unconnected-(SV7-Pad8)") (class "Default")
      (node (ref "SV7") (pin "8") (pinfunction "8_8") (pintype "passive"))
    )
    (net (code "209") (name "unconnected-(SV7-Pad9)") (class "Default")
      (node (ref "SV7") (pin "9") (pinfunction "9_9") (pintype "passive"))
    )
    (net (code "210") (name "unconnected-(SV7-Pad10)") (class "Default")
      (node (ref "SV7") (pin "10") (pinfunction "10_10") (pintype "passive"))
    )
    (net (code "211") (name "unconnected-(SV8-Pad1)") (class "Default")
      (node (ref "SV8") (pin "1") (pinfunction "1_1") (pintype "passive"))
    )
    (net (code "212") (name "unconnected-(SV8-Pad2)") (class "Default")
      (node (ref "SV8") (pin "2") (pinfunction "2_2") (pintype "passive"))
    )
    (net (code "213") (name "unconnected-(SV8-Pad3)") (class "Default")
      (node (ref "SV8") (pin "3") (pinfunction "3_3") (pintype "passive"))
    )
    (net (code "214") (name "unconnected-(SV8-Pad4)") (class "Default")
      (node (ref "SV8") (pin "4") (pinfunction "4_4") (pintype "passive"))
    )
    (net (code "215") (name "unconnected-(SV8-Pad5)") (class "Default")
      (node (ref "SV8") (pin "5") (pinfunction "5_5") (pintype "passive"))
    )
    (net (code "216") (name "unconnected-(SV8-Pad6)") (class "Default")
      (node (ref "SV8") (pin "6") (pinfunction "6_6") (pintype "passive"))
    )
    (net (code "217") (name "unconnected-(SV8-Pad7)") (class "Default")
      (node (ref "SV8") (pin "7") (pinfunction "7_7") (pintype "passive"))
    )
    (net (code "218") (name "unconnected-(SV8-Pad8)") (class "Default")
      (node (ref "SV8") (pin "8") (pinfunction "8_8") (pintype "passive"))
    )
    (net (code "219") (name "unconnected-(SV8-Pad9)") (class "Default")
      (node (ref "SV8") (pin "9") (pinfunction "9_9") (pintype "passive"))
    )
    (net (code "220") (name "unconnected-(SV8-Pad10)") (class "Default")
      (node (ref "SV8") (pin "10") (pinfunction "10_10") (pintype "passive"))
    )
    (net (code "221") (name "unconnected-(SV9-Pad10)") (class "Default")
      (node (ref "SV9") (pin "10") (pinfunction "10_10") (pintype "passive"))
    )
    (net (code "222") (name "unconnected-(SV10-Pad1)") (class "Default")
      (node (ref "SV10") (pin "1") (pinfunction "1_1") (pintype "passive"))
    )
    (net (code "223") (name "unconnected-(SV10-Pad2)") (class "Default")
      (node (ref "SV10") (pin "2") (pinfunction "2_2") (pintype "passive"))
    )
    (net (code "224") (name "unconnected-(SV10-Pad3)") (class "Default")
      (node (ref "SV10") (pin "3") (pinfunction "3_3") (pintype "passive"))
    )
    (net (code "225") (name "unconnected-(SV10-Pad4)") (class "Default")
      (node (ref "SV10") (pin "4") (pinfunction "4_4") (pintype "passive"))
    )
    (net (code "226") (name "unconnected-(SV10-Pad5)") (class "Default")
      (node (ref "SV10") (pin "5") (pinfunction "5_5") (pintype "passive"))
    )
    (net (code "227") (name "unconnected-(SV10-Pad6)") (class "Default")
      (node (ref "SV10") (pin "6") (pinfunction "6_6") (pintype "passive"))
    )
    (net (code "228") (name "unconnected-(SV10-Pad7)") (class "Default")
      (node (ref "SV10") (pin "7") (pinfunction "7_7") (pintype "passive"))
    )
    (net (code "229") (name "unconnected-(SV10-Pad8)") (class "Default")
      (node (ref "SV10") (pin "8") (pinfunction "8_8") (pintype "passive"))
    )
    (net (code "230") (name "unconnected-(SV10-Pad9)") (class "Default")
      (node (ref "SV10") (pin "9") (pinfunction "9_9") (pintype "passive"))
    )
    (net (code "231") (name "unconnected-(SV10-Pad10)") (class "Default")
      (node (ref "SV10") (pin "10") (pinfunction "10_10") (pintype "passive"))
    )
    (net (code "232") (name "unconnected-(SV13-Pad10)") (class "Default")
      (node (ref "SV13") (pin "10") (pinfunction "10_10") (pintype "passive"))
    )
    (net (code "233") (name "unconnected-(SV14-Pad1)") (class "Default")
      (node (ref "SV14") (pin "1") (pinfunction "1_1") (pintype "passive"))
    )
    (net (code "234") (name "unconnected-(SV14-Pad2)") (class "Default")
      (node (ref "SV14") (pin "2") (pinfunction "2_2") (pintype "passive"))
    )
    (net (code "235") (name "unconnected-(SV14-Pad3)") (class "Default")
      (node (ref "SV14") (pin "3") (pinfunction "3_3") (pintype "passive"))
    )
    (net (code "236") (name "unconnected-(SV14-Pad4)") (class "Default")
      (node (ref "SV14") (pin "4") (pinfunction "4_4") (pintype "passive"))
    )
    (net (code "237") (name "unconnected-(SV14-Pad5)") (class "Default")
      (node (ref "SV14") (pin "5") (pinfunction "5_5") (pintype "passive"))
    )
    (net (code "238") (name "unconnected-(SV14-Pad6)") (class "Default")
      (node (ref "SV14") (pin "6") (pinfunction "6_6") (pintype "passive"))
    )
    (net (code "239") (name "unconnected-(SV14-Pad7)") (class "Default")
      (node (ref "SV14") (pin "7") (pinfunction "7_7") (pintype "passive"))
    )
    (net (code "240") (name "unconnected-(SV14-Pad8)") (class "Default")
      (node (ref "SV14") (pin "8") (pinfunction "8_8") (pintype "passive"))
    )
    (net (code "241") (name "unconnected-(SV14-Pad9)") (class "Default")
      (node (ref "SV14") (pin "9") (pinfunction "9_9") (pintype "passive"))
    )
    (net (code "242") (name "unconnected-(SV14-Pad10)") (class "Default")
      (node (ref "SV14") (pin "10") (pinfunction "10_10") (pintype "passive"))
    )
    (net (code "243") (name "unconnected-(SV15-Pad9)") (class "Default")
      (node (ref "SV15") (pin "9") (pinfunction "9_9") (pintype "passive"))
    )
    (net (code "244") (name "unconnected-(SV15-Pad10)") (class "Default")
      (node (ref "SV15") (pin "10") (pinfunction "10_10") (pintype "passive"))
    )
    (net (code "245") (name "unconnected-(SV16-Pad1)") (class "Default")
      (node (ref "SV16") (pin "1") (pinfunction "1_1") (pintype "passive"))
    )
    (net (code "246") (name "unconnected-(SV16-Pad2)") (class "Default")
      (node (ref "SV16") (pin "2") (pinfunction "2_2") (pintype "passive"))
    )
    (net (code "247") (name "unconnected-(SV16-Pad3)") (class "Default")
      (node (ref "SV16") (pin "3") (pinfunction "3_3") (pintype "passive"))
    )
    (net (code "248") (name "unconnected-(SV16-Pad4)") (class "Default")
      (node (ref "SV16") (pin "4") (pinfunction "4_4") (pintype "passive"))
    )
    (net (code "249") (name "unconnected-(SV16-Pad5)") (class "Default")
      (node (ref "SV16") (pin "5") (pinfunction "5_5") (pintype "passive"))
    )
    (net (code "250") (name "unconnected-(SV16-Pad6)") (class "Default")
      (node (ref "SV16") (pin "6") (pinfunction "6_6") (pintype "passive"))
    )
    (net (code "251") (name "unconnected-(SV16-Pad7)") (class "Default")
      (node (ref "SV16") (pin "7") (pinfunction "7_7") (pintype "passive"))
    )
    (net (code "252") (name "unconnected-(SV16-Pad8)") (class "Default")
      (node (ref "SV16") (pin "8") (pinfunction "8_8") (pintype "passive"))
    )
    (net (code "253") (name "unconnected-(SV16-Pad9)") (class "Default")
      (node (ref "SV16") (pin "9") (pinfunction "9_9") (pintype "passive"))
    )
    (net (code "254") (name "unconnected-(SV16-Pad10)") (class "Default")
      (node (ref "SV16") (pin "10") (pinfunction "10_10") (pintype "passive"))
    )
    (net (code "255") (name "unconnected-(U1-VBAT-Pad1)") (class "Default")
      (node (ref "U1") (pin "1") (pinfunction "VBAT_1") (pintype "bidirectional"))
    )
    (net (code "256") (name "unconnected-(X1-Pad1)") (class "Default")
      (node (ref "X1") (pin "1") (pinfunction "1_1") (pintype "input"))
    )
  )
)
